# SCH_Ortho90_2023-07-25.net
KiCad netlist of a schematic drawn in EasyEDA
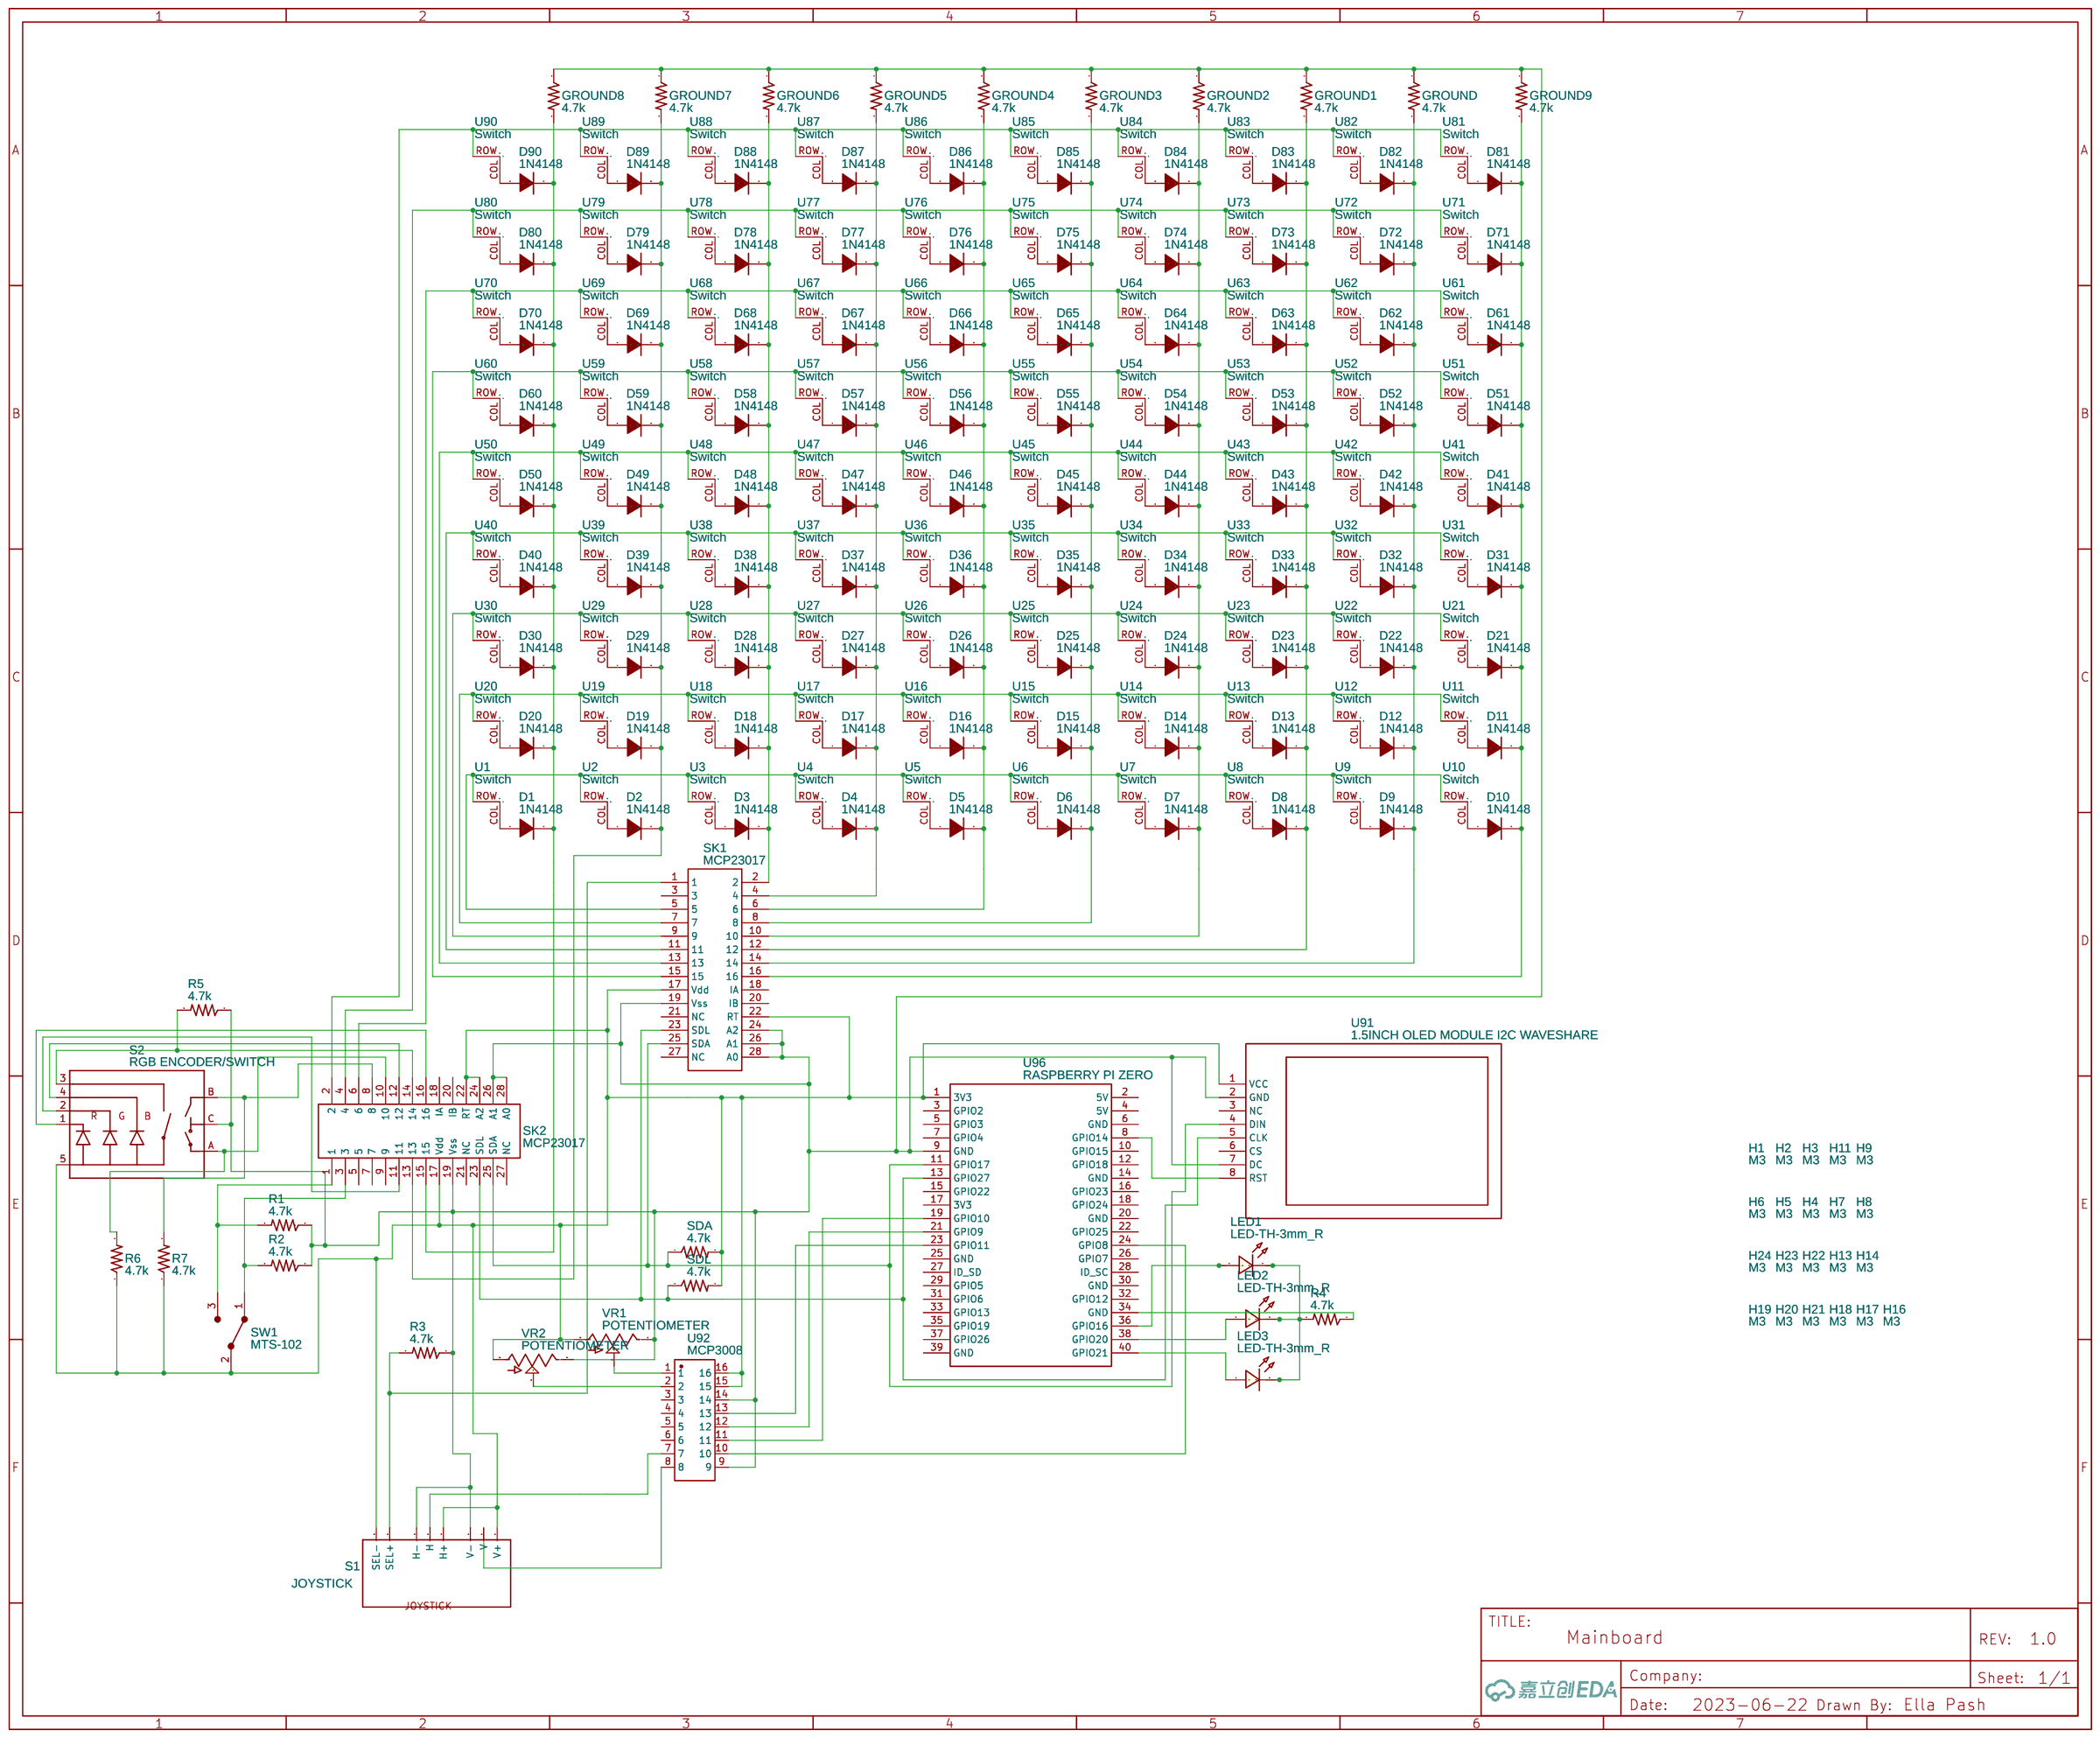
[diagram p0: schematic sheet]

(export (version "E")
  (design (tool "Eeschema 10.0.6"))
  (components
    (comp (ref "D1")
      (value "1N4148")
      (fields (field (name "BOM_Supplier Part") "C14516"))
      (libsource (lib "") (part "1N4148"))
    )
    (comp (ref "D2")
      (value "1N4148")
      (fields (field (name "BOM_Supplier Part") "C14516"))
      (libsource (lib "") (part "1N4148"))
    )
    (comp (ref "D3")
      (value "1N4148")
      (fields (field (name "BOM_Supplier Part") "C14516"))
      (libsource (lib "") (part "1N4148"))
    )
    (comp (ref "D4")
      (value "1N4148")
      (fields (field (name "BOM_Supplier Part") "C14516"))
      (libsource (lib "") (part "1N4148"))
    )
    (comp (ref "D5")
      (value "1N4148")
      (fields (field (name "BOM_Supplier Part") "C14516"))
      (libsource (lib "") (part "1N4148"))
    )
    (comp (ref "D6")
      (value "1N4148")
      (fields (field (name "BOM_Supplier Part") "C14516"))
      (libsource (lib "") (part "1N4148"))
    )
    (comp (ref "D7")
      (value "1N4148")
      (fields (field (name "BOM_Supplier Part") "C14516"))
      (libsource (lib "") (part "1N4148"))
    )
    (comp (ref "D8")
      (value "1N4148")
      (fields (field (name "BOM_Supplier Part") "C14516"))
      (libsource (lib "") (part "1N4148"))
    )
    (comp (ref "D9")
      (value "1N4148")
      (fields (field (name "BOM_Supplier Part") "C14516"))
      (libsource (lib "") (part "1N4148"))
    )
    (comp (ref "D10")
      (value "1N4148")
      (fields (field (name "BOM_Supplier Part") "C14516"))
      (libsource (lib "") (part "1N4148"))
    )
    (comp (ref "D11")
      (value "1N4148")
      (fields (field (name "BOM_Supplier Part") "C14516"))
      (libsource (lib "") (part "1N4148"))
    )
    (comp (ref "D12")
      (value "1N4148")
      (fields (field (name "BOM_Supplier Part") "C14516"))
      (libsource (lib "") (part "1N4148"))
    )
    (comp (ref "D13")
      (value "1N4148")
      (fields (field (name "BOM_Supplier Part") "C14516"))
      (libsource (lib "") (part "1N4148"))
    )
    (comp (ref "D14")
      (value "1N4148")
      (fields (field (name "BOM_Supplier Part") "C14516"))
      (libsource (lib "") (part "1N4148"))
    )
    (comp (ref "D15")
      (value "1N4148")
      (fields (field (name "BOM_Supplier Part") "C14516"))
      (libsource (lib "") (part "1N4148"))
    )
    (comp (ref "D16")
      (value "1N4148")
      (fields (field (name "BOM_Supplier Part") "C14516"))
      (libsource (lib "") (part "1N4148"))
    )
    (comp (ref "D17")
      (value "1N4148")
      (fields (field (name "BOM_Supplier Part") "C14516"))
      (libsource (lib "") (part "1N4148"))
    )
    (comp (ref "D18")
      (value "1N4148")
      (fields (field (name "BOM_Supplier Part") "C14516"))
      (libsource (lib "") (part "1N4148"))
    )
    (comp (ref "D19")
      (value "1N4148")
      (fields (field (name "BOM_Supplier Part") "C14516"))
      (libsource (lib "") (part "1N4148"))
    )
    (comp (ref "D20")
      (value "1N4148")
      (fields (field (name "BOM_Supplier Part") "C14516"))
      (libsource (lib "") (part "1N4148"))
    )
    (comp (ref "D21")
      (value "1N4148")
      (fields (field (name "BOM_Supplier Part") "C14516"))
      (libsource (lib "") (part "1N4148"))
    )
    (comp (ref "D22")
      (value "1N4148")
      (fields (field (name "BOM_Supplier Part") "C14516"))
      (libsource (lib "") (part "1N4148"))
    )
    (comp (ref "D23")
      (value "1N4148")
      (fields (field (name "BOM_Supplier Part") "C14516"))
      (libsource (lib "") (part "1N4148"))
    )
    (comp (ref "D24")
      (value "1N4148")
      (fields (field (name "BOM_Supplier Part") "C14516"))
      (libsource (lib "") (part "1N4148"))
    )
    (comp (ref "D25")
      (value "1N4148")
      (fields (field (name "BOM_Supplier Part") "C14516"))
      (libsource (lib "") (part "1N4148"))
    )
    (comp (ref "D26")
      (value "1N4148")
      (fields (field (name "BOM_Supplier Part") "C14516"))
      (libsource (lib "") (part "1N4148"))
    )
    (comp (ref "D27")
      (value "1N4148")
      (fields (field (name "BOM_Supplier Part") "C14516"))
      (libsource (lib "") (part "1N4148"))
    )
    (comp (ref "D28")
      (value "1N4148")
      (fields (field (name "BOM_Supplier Part") "C14516"))
      (libsource (lib "") (part "1N4148"))
    )
    (comp (ref "D29")
      (value "1N4148")
      (fields (field (name "BOM_Supplier Part") "C14516"))
      (libsource (lib "") (part "1N4148"))
    )
    (comp (ref "D30")
      (value "1N4148")
      (fields (field (name "BOM_Supplier Part") "C14516"))
      (libsource (lib "") (part "1N4148"))
    )
    (comp (ref "D31")
      (value "1N4148")
      (fields (field (name "BOM_Supplier Part") "C14516"))
      (libsource (lib "") (part "1N4148"))
    )
    (comp (ref "D32")
      (value "1N4148")
      (fields (field (name "BOM_Supplier Part") "C14516"))
      (libsource (lib "") (part "1N4148"))
    )
    (comp (ref "D33")
      (value "1N4148")
      (fields (field (name "BOM_Supplier Part") "C14516"))
      (libsource (lib "") (part "1N4148"))
    )
    (comp (ref "D34")
      (value "1N4148")
      (fields (field (name "BOM_Supplier Part") "C14516"))
      (libsource (lib "") (part "1N4148"))
    )
    (comp (ref "D35")
      (value "1N4148")
      (fields (field (name "BOM_Supplier Part") "C14516"))
      (libsource (lib "") (part "1N4148"))
    )
    (comp (ref "D36")
      (value "1N4148")
      (fields (field (name "BOM_Supplier Part") "C14516"))
      (libsource (lib "") (part "1N4148"))
    )
    (comp (ref "D37")
      (value "1N4148")
      (fields (field (name "BOM_Supplier Part") "C14516"))
      (libsource (lib "") (part "1N4148"))
    )
    (comp (ref "D38")
      (value "1N4148")
      (fields (field (name "BOM_Supplier Part") "C14516"))
      (libsource (lib "") (part "1N4148"))
    )
    (comp (ref "D39")
      (value "1N4148")
      (fields (field (name "BOM_Supplier Part") "C14516"))
      (libsource (lib "") (part "1N4148"))
    )
    (comp (ref "D40")
      (value "1N4148")
      (fields (field (name "BOM_Supplier Part") "C14516"))
      (libsource (lib "") (part "1N4148"))
    )
    (comp (ref "D41")
      (value "1N4148")
      (fields (field (name "BOM_Supplier Part") "C14516"))
      (libsource (lib "") (part "1N4148"))
    )
    (comp (ref "D42")
      (value "1N4148")
      (fields (field (name "BOM_Supplier Part") "C14516"))
      (libsource (lib "") (part "1N4148"))
    )
    (comp (ref "D43")
      (value "1N4148")
      (fields (field (name "BOM_Supplier Part") "C14516"))
      (libsource (lib "") (part "1N4148"))
    )
    (comp (ref "D44")
      (value "1N4148")
      (fields (field (name "BOM_Supplier Part") "C14516"))
      (libsource (lib "") (part "1N4148"))
    )
    (comp (ref "D45")
      (value "1N4148")
      (fields (field (name "BOM_Supplier Part") "C14516"))
      (libsource (lib "") (part "1N4148"))
    )
    (comp (ref "D46")
      (value "1N4148")
      (fields (field (name "BOM_Supplier Part") "C14516"))
      (libsource (lib "") (part "1N4148"))
    )
    (comp (ref "D47")
      (value "1N4148")
      (fields (field (name "BOM_Supplier Part") "C14516"))
      (libsource (lib "") (part "1N4148"))
    )
    (comp (ref "D48")
      (value "1N4148")
      (fields (field (name "BOM_Supplier Part") "C14516"))
      (libsource (lib "") (part "1N4148"))
    )
    (comp (ref "D49")
      (value "1N4148")
      (fields (field (name "BOM_Supplier Part") "C14516"))
      (libsource (lib "") (part "1N4148"))
    )
    (comp (ref "D50")
      (value "1N4148")
      (fields (field (name "BOM_Supplier Part") "C14516"))
      (libsource (lib "") (part "1N4148"))
    )
    (comp (ref "D51")
      (value "1N4148")
      (fields (field (name "BOM_Supplier Part") "C14516"))
      (libsource (lib "") (part "1N4148"))
    )
    (comp (ref "D52")
      (value "1N4148")
      (fields (field (name "BOM_Supplier Part") "C14516"))
      (libsource (lib "") (part "1N4148"))
    )
    (comp (ref "D53")
      (value "1N4148")
      (fields (field (name "BOM_Supplier Part") "C14516"))
      (libsource (lib "") (part "1N4148"))
    )
    (comp (ref "D54")
      (value "1N4148")
      (fields (field (name "BOM_Supplier Part") "C14516"))
      (libsource (lib "") (part "1N4148"))
    )
    (comp (ref "D55")
      (value "1N4148")
      (fields (field (name "BOM_Supplier Part") "C14516"))
      (libsource (lib "") (part "1N4148"))
    )
    (comp (ref "D56")
      (value "1N4148")
      (fields (field (name "BOM_Supplier Part") "C14516"))
      (libsource (lib "") (part "1N4148"))
    )
    (comp (ref "D57")
      (value "1N4148")
      (fields (field (name "BOM_Supplier Part") "C14516"))
      (libsource (lib "") (part "1N4148"))
    )
    (comp (ref "D58")
      (value "1N4148")
      (fields (field (name "BOM_Supplier Part") "C14516"))
      (libsource (lib "") (part "1N4148"))
    )
    (comp (ref "D59")
      (value "1N4148")
      (fields (field (name "BOM_Supplier Part") "C14516"))
      (libsource (lib "") (part "1N4148"))
    )
    (comp (ref "D60")
      (value "1N4148")
      (fields (field (name "BOM_Supplier Part") "C14516"))
      (libsource (lib "") (part "1N4148"))
    )
    (comp (ref "D61")
      (value "1N4148")
      (fields (field (name "BOM_Supplier Part") "C14516"))
      (libsource (lib "") (part "1N4148"))
    )
    (comp (ref "D62")
      (value "1N4148")
      (fields (field (name "BOM_Supplier Part") "C14516"))
      (libsource (lib "") (part "1N4148"))
    )
    (comp (ref "D63")
      (value "1N4148")
      (fields (field (name "BOM_Supplier Part") "C14516"))
      (libsource (lib "") (part "1N4148"))
    )
    (comp (ref "D64")
      (value "1N4148")
      (fields (field (name "BOM_Supplier Part") "C14516"))
      (libsource (lib "") (part "1N4148"))
    )
    (comp (ref "D65")
      (value "1N4148")
      (fields (field (name "BOM_Supplier Part") "C14516"))
      (libsource (lib "") (part "1N4148"))
    )
    (comp (ref "D66")
      (value "1N4148")
      (fields (field (name "BOM_Supplier Part") "C14516"))
      (libsource (lib "") (part "1N4148"))
    )
    (comp (ref "D67")
      (value "1N4148")
      (fields (field (name "BOM_Supplier Part") "C14516"))
      (libsource (lib "") (part "1N4148"))
    )
    (comp (ref "D68")
      (value "1N4148")
      (fields (field (name "BOM_Supplier Part") "C14516"))
      (libsource (lib "") (part "1N4148"))
    )
    (comp (ref "D69")
      (value "1N4148")
      (fields (field (name "BOM_Supplier Part") "C14516"))
      (libsource (lib "") (part "1N4148"))
    )
    (comp (ref "D70")
      (value "1N4148")
      (fields (field (name "BOM_Supplier Part") "C14516"))
      (libsource (lib "") (part "1N4148"))
    )
    (comp (ref "D71")
      (value "1N4148")
      (fields (field (name "BOM_Supplier Part") "C14516"))
      (libsource (lib "") (part "1N4148"))
    )
    (comp (ref "D72")
      (value "1N4148")
      (fields (field (name "BOM_Supplier Part") "C14516"))
      (libsource (lib "") (part "1N4148"))
    )
    (comp (ref "D73")
      (value "1N4148")
      (fields (field (name "BOM_Supplier Part") "C14516"))
      (libsource (lib "") (part "1N4148"))
    )
    (comp (ref "D74")
      (value "1N4148")
      (fields (field (name "BOM_Supplier Part") "C14516"))
      (libsource (lib "") (part "1N4148"))
    )
    (comp (ref "D75")
      (value "1N4148")
      (fields (field (name "BOM_Supplier Part") "C14516"))
      (libsource (lib "") (part "1N4148"))
    )
    (comp (ref "D76")
      (value "1N4148")
      (fields (field (name "BOM_Supplier Part") "C14516"))
      (libsource (lib "") (part "1N4148"))
    )
    (comp (ref "D77")
      (value "1N4148")
      (fields (field (name "BOM_Supplier Part") "C14516"))
      (libsource (lib "") (part "1N4148"))
    )
    (comp (ref "D78")
      (value "1N4148")
      (fields (field (name "BOM_Supplier Part") "C14516"))
      (libsource (lib "") (part "1N4148"))
    )
    (comp (ref "D79")
      (value "1N4148")
      (fields (field (name "BOM_Supplier Part") "C14516"))
      (libsource (lib "") (part "1N4148"))
    )
    (comp (ref "D80")
      (value "1N4148")
      (fields (field (name "BOM_Supplier Part") "C14516"))
      (libsource (lib "") (part "1N4148"))
    )
    (comp (ref "D81")
      (value "1N4148")
      (fields (field (name "BOM_Supplier Part") "C14516"))
      (libsource (lib "") (part "1N4148"))
    )
    (comp (ref "D82")
      (value "1N4148")
      (fields (field (name "BOM_Supplier Part") "C14516"))
      (libsource (lib "") (part "1N4148"))
    )
    (comp (ref "D83")
      (value "1N4148")
      (fields (field (name "BOM_Supplier Part") "C14516"))
      (libsource (lib "") (part "1N4148"))
    )
    (comp (ref "D84")
      (value "1N4148")
      (fields (field (name "BOM_Supplier Part") "C14516"))
      (libsource (lib "") (part "1N4148"))
    )
    (comp (ref "D85")
      (value "1N4148")
      (fields (field (name "BOM_Supplier Part") "C14516"))
      (libsource (lib "") (part "1N4148"))
    )
    (comp (ref "D86")
      (value "1N4148")
      (fields (field (name "BOM_Supplier Part") "C14516"))
      (libsource (lib "") (part "1N4148"))
    )
    (comp (ref "D87")
      (value "1N4148")
      (fields (field (name "BOM_Supplier Part") "C14516"))
      (libsource (lib "") (part "1N4148"))
    )
    (comp (ref "D88")
      (value "1N4148")
      (fields (field (name "BOM_Supplier Part") "C14516"))
      (libsource (lib "") (part "1N4148"))
    )
    (comp (ref "D89")
      (value "1N4148")
      (fields (field (name "BOM_Supplier Part") "C14516"))
      (libsource (lib "") (part "1N4148"))
    )
    (comp (ref "D90")
      (value "1N4148")
      (fields (field (name "BOM_Supplier Part") "C14516"))
      (libsource (lib "") (part "1N4148"))
    )
    (comp (ref "GROUND") (value "4.7k") (libsource (lib "") (part "RESISTORKIT_1")))
    (comp (ref "GROUND1") (value "4.7k") (libsource (lib "") (part "RESISTORKIT_1")))
    (comp (ref "GROUND2") (value "4.7k") (libsource (lib "") (part "RESISTORKIT_1")))
    (comp (ref "GROUND3") (value "4.7k") (libsource (lib "") (part "RESISTORKIT_1")))
    (comp (ref "GROUND4") (value "4.7k") (libsource (lib "") (part "RESISTORKIT_1")))
    (comp (ref "GROUND5") (value "4.7k") (libsource (lib "") (part "RESISTORKIT_1")))
    (comp (ref "GROUND6") (value "4.7k") (libsource (lib "") (part "RESISTORKIT_1")))
    (comp (ref "GROUND7") (value "4.7k") (libsource (lib "") (part "RESISTORKIT_1")))
    (comp (ref "GROUND8") (value "4.7k") (libsource (lib "") (part "RESISTORKIT_1")))
    (comp (ref "GROUND9") (value "4.7k") (libsource (lib "") (part "RESISTORKIT_1")))
    (comp (ref "H1") (value "M3") (libsource (lib "") (part "MountingHole_3.2mm_M3")))
    (comp (ref "H2") (value "M3") (libsource (lib "") (part "MountingHole_3.2mm_M3")))
    (comp (ref "H3") (value "M3") (libsource (lib "") (part "MountingHole_3.2mm_M3")))
    (comp (ref "H4") (value "M3") (libsource (lib "") (part "MountingHole_3.2mm_M3")))
    (comp (ref "H5") (value "M3") (libsource (lib "") (part "MountingHole_3.2mm_M3")))
    (comp (ref "H6") (value "M3") (libsource (lib "") (part "MountingHole_3.2mm_M3")))
    (comp (ref "H7") (value "M3") (libsource (lib "") (part "MountingHole_3.2mm_M3")))
    (comp (ref "H8") (value "M3") (libsource (lib "") (part "MountingHole_3.2mm_M3")))
    (comp (ref "H9") (value "M3") (libsource (lib "") (part "MountingHole_3.2mm_M3")))
    (comp (ref "H11") (value "M3") (libsource (lib "") (part "MountingHole_3.2mm_M3")))
    (comp (ref "H13") (value "M3") (libsource (lib "") (part "MountingHole_3.2mm_M3")))
    (comp (ref "H14") (value "M3") (libsource (lib "") (part "MountingHole_3.2mm_M3")))
    (comp (ref "H16") (value "M3") (libsource (lib "") (part "MountingHole_3.2mm_M3")))
    (comp (ref "H17") (value "M3") (libsource (lib "") (part "MountingHole_3.2mm_M3")))
    (comp (ref "H18") (value "M3") (libsource (lib "") (part "MountingHole_3.2mm_M3")))
    (comp (ref "H19") (value "M3") (libsource (lib "") (part "MountingHole_3.2mm_M3")))
    (comp (ref "H20") (value "M3") (libsource (lib "") (part "MountingHole_3.2mm_M3")))
    (comp (ref "H21") (value "M3") (libsource (lib "") (part "MountingHole_3.2mm_M3")))
    (comp (ref "H22") (value "M3") (libsource (lib "") (part "MountingHole_3.2mm_M3")))
    (comp (ref "H23") (value "M3") (libsource (lib "") (part "MountingHole_3.2mm_M3")))
    (comp (ref "H24") (value "M3") (libsource (lib "") (part "MountingHole_3.2mm_M3")))
    (comp (ref "LED1")
      (value "LED-TH-3mm_R")
      (fields
        (field (name "BOM_Manufacturer Part") "204-10SDRD/S530-A3-L")
        (field (name "BOM_Supplier Part") "C84774")
      )
      (libsource (lib "") (part "LED-TH-3mm_R"))
    )
    (comp (ref "LED2")
      (value "LED-TH-3mm_R")
      (fields
        (field (name "BOM_Manufacturer Part") "204-10SDRD/S530-A3-L")
        (field (name "BOM_Supplier Part") "C84774")
      )
      (libsource (lib "") (part "LED-TH-3mm_R"))
    )
    (comp (ref "LED3")
      (value "LED-TH-3mm_R")
      (fields
        (field (name "BOM_Manufacturer Part") "204-10SDRD/S530-A3-L")
        (field (name "BOM_Supplier Part") "C84774")
      )
      (libsource (lib "") (part "LED-TH-3mm_R"))
    )
    (comp (ref "R1") (value "4.7k") (libsource (lib "") (part "RESISTORKIT")))
    (comp (ref "R2") (value "4.7k") (libsource (lib "") (part "RESISTORKIT")))
    (comp (ref "R3") (value "4.7k") (libsource (lib "") (part "RESISTORKIT")))
    (comp (ref "R4") (value "4.7k") (libsource (lib "") (part "RESISTORKIT")))
    (comp (ref "R5") (value "4.7k") (libsource (lib "") (part "RESISTORKIT")))
    (comp (ref "R6") (value "4.7k") (libsource (lib "") (part "RESISTORKIT_2")))
    (comp (ref "R7") (value "4.7k") (libsource (lib "") (part "RESISTORKIT_2")))
    (comp (ref "S1") (value "JOYSTICK") (libsource (lib "") (part "JOYSTICK_THUMB")))
    (comp (ref "S2") (value "RGB ENCODER/SWITCH") (libsource (lib "") (part "ENCODER-RGB-SWITCH-NO_NUT")))
    (comp (ref "SDA") (value "4.7k") (libsource (lib "") (part "RESISTORKIT_3")))
    (comp (ref "SDL") (value "4.7k") (libsource (lib "") (part "RESISTORKIT_4")))
    (comp (ref "SK1")
      (value "MCP23017")
      (fields (field (name "BOM_Manufacturer Part") "IC-28P窄") (field (name "BOM_Supplier Part") "C16653"))
      (libsource (lib "") (part "IC seat_1"))
    )
    (comp (ref "SK2")
      (value "MCP23017")
      (fields (field (name "BOM_Manufacturer Part") "IC-28P窄") (field (name "BOM_Supplier Part") "C16653"))
      (libsource (lib "") (part "IC seat"))
    )
    (comp (ref "SW1")
      (value "MTS-102")
      (fields
        (field (name "BOM_Manufacturer Part") "New SchematicLib")
        (field (name "BOM_Supplier Part") "SMTS-202-A2")
      )
      (libsource (lib "") (part "MTS-102"))
    )
    (comp (ref "U1") (value "Switch") (libsource (lib "") (part "Switch")))
    (comp (ref "U2") (value "Switch") (libsource (lib "") (part "Switch")))
    (comp (ref "U3") (value "Switch") (libsource (lib "") (part "Switch")))
    (comp (ref "U4") (value "Switch") (libsource (lib "") (part "Switch")))
    (comp (ref "U5") (value "Switch") (libsource (lib "") (part "Switch")))
    (comp (ref "U6") (value "Switch") (libsource (lib "") (part "Switch")))
    (comp (ref "U7") (value "Switch") (libsource (lib "") (part "Switch")))
    (comp (ref "U8") (value "Switch") (libsource (lib "") (part "Switch")))
    (comp (ref "U9") (value "Switch") (libsource (lib "") (part "Switch")))
    (comp (ref "U10") (value "Switch") (libsource (lib "") (part "Switch")))
    (comp (ref "U11") (value "Switch") (libsource (lib "") (part "Switch")))
    (comp (ref "U12") (value "Switch") (libsource (lib "") (part "Switch")))
    (comp (ref "U13") (value "Switch") (libsource (lib "") (part "Switch")))
    (comp (ref "U14") (value "Switch") (libsource (lib "") (part "Switch")))
    (comp (ref "U15") (value "Switch") (libsource (lib "") (part "Switch")))
    (comp (ref "U16") (value "Switch") (libsource (lib "") (part "Switch")))
    (comp (ref "U17") (value "Switch") (libsource (lib "") (part "Switch")))
    (comp (ref "U18") (value "Switch") (libsource (lib "") (part "Switch")))
    (comp (ref "U19") (value "Switch") (libsource (lib "") (part "Switch")))
    (comp (ref "U20") (value "Switch") (libsource (lib "") (part "Switch")))
    (comp (ref "U21") (value "Switch") (libsource (lib "") (part "Switch")))
    (comp (ref "U22") (value "Switch") (libsource (lib "") (part "Switch")))
    (comp (ref "U23") (value "Switch") (libsource (lib "") (part "Switch")))
    (comp (ref "U24") (value "Switch") (libsource (lib "") (part "Switch")))
    (comp (ref "U25") (value "Switch") (libsource (lib "") (part "Switch")))
    (comp (ref "U26") (value "Switch") (libsource (lib "") (part "Switch")))
    (comp (ref "U27") (value "Switch") (libsource (lib "") (part "Switch")))
    (comp (ref "U28") (value "Switch") (libsource (lib "") (part "Switch")))
    (comp (ref "U29") (value "Switch") (libsource (lib "") (part "Switch")))
    (comp (ref "U30") (value "Switch") (libsource (lib "") (part "Switch")))
    (comp (ref "U31") (value "Switch") (libsource (lib "") (part "Switch")))
    (comp (ref "U32") (value "Switch") (libsource (lib "") (part "Switch")))
    (comp (ref "U33") (value "Switch") (libsource (lib "") (part "Switch")))
    (comp (ref "U34") (value "Switch") (libsource (lib "") (part "Switch")))
    (comp (ref "U35") (value "Switch") (libsource (lib "") (part "Switch")))
    (comp (ref "U36") (value "Switch") (libsource (lib "") (part "Switch")))
    (comp (ref "U37") (value "Switch") (libsource (lib "") (part "Switch")))
    (comp (ref "U38") (value "Switch") (libsource (lib "") (part "Switch")))
    (comp (ref "U39") (value "Switch") (libsource (lib "") (part "Switch")))
    (comp (ref "U40") (value "Switch") (libsource (lib "") (part "Switch")))
    (comp (ref "U41") (value "Switch") (libsource (lib "") (part "Switch")))
    (comp (ref "U42") (value "Switch") (libsource (lib "") (part "Switch")))
    (comp (ref "U43") (value "Switch") (libsource (lib "") (part "Switch")))
    (comp (ref "U44") (value "Switch") (libsource (lib "") (part "Switch")))
    (comp (ref "U45") (value "Switch") (libsource (lib "") (part "Switch")))
    (comp (ref "U46") (value "Switch") (libsource (lib "") (part "Switch")))
    (comp (ref "U47") (value "Switch") (libsource (lib "") (part "Switch")))
    (comp (ref "U48") (value "Switch") (libsource (lib "") (part "Switch")))
    (comp (ref "U49") (value "Switch") (libsource (lib "") (part "Switch")))
    (comp (ref "U50") (value "Switch") (libsource (lib "") (part "Switch")))
    (comp (ref "U51") (value "Switch") (libsource (lib "") (part "Switch")))
    (comp (ref "U52") (value "Switch") (libsource (lib "") (part "Switch")))
    (comp (ref "U53") (value "Switch") (libsource (lib "") (part "Switch")))
    (comp (ref "U54") (value "Switch") (libsource (lib "") (part "Switch")))
    (comp (ref "U55") (value "Switch") (libsource (lib "") (part "Switch")))
    (comp (ref "U56") (value "Switch") (libsource (lib "") (part "Switch")))
    (comp (ref "U57") (value "Switch") (libsource (lib "") (part "Switch")))
    (comp (ref "U58") (value "Switch") (libsource (lib "") (part "Switch")))
    (comp (ref "U59") (value "Switch") (libsource (lib "") (part "Switch")))
    (comp (ref "U60") (value "Switch") (libsource (lib "") (part "Switch")))
    (comp (ref "U61") (value "Switch") (libsource (lib "") (part "Switch")))
    (comp (ref "U62") (value "Switch") (libsource (lib "") (part "Switch")))
    (comp (ref "U63") (value "Switch") (libsource (lib "") (part "Switch")))
    (comp (ref "U64") (value "Switch") (libsource (lib "") (part "Switch")))
    (comp (ref "U65") (value "Switch") (libsource (lib "") (part "Switch")))
    (comp (ref "U66") (value "Switch") (libsource (lib "") (part "Switch")))
    (comp (ref "U67") (value "Switch") (libsource (lib "") (part "Switch")))
    (comp (ref "U68") (value "Switch") (libsource (lib "") (part "Switch")))
    (comp (ref "U69") (value "Switch") (libsource (lib "") (part "Switch")))
    (comp (ref "U70") (value "Switch") (libsource (lib "") (part "Switch")))
    (comp (ref "U71") (value "Switch") (libsource (lib "") (part "Switch")))
    (comp (ref "U72") (value "Switch") (libsource (lib "") (part "Switch")))
    (comp (ref "U73") (value "Switch") (libsource (lib "") (part "Switch")))
    (comp (ref "U74") (value "Switch") (libsource (lib "") (part "Switch")))
    (comp (ref "U75") (value "Switch") (libsource (lib "") (part "Switch")))
    (comp (ref "U76") (value "Switch") (libsource (lib "") (part "Switch")))
    (comp (ref "U77") (value "Switch") (libsource (lib "") (part "Switch")))
    (comp (ref "U78") (value "Switch") (libsource (lib "") (part "Switch")))
    (comp (ref "U79") (value "Switch") (libsource (lib "") (part "Switch")))
    (comp (ref "U80") (value "Switch") (libsource (lib "") (part "Switch")))
    (comp (ref "U81") (value "Switch") (libsource (lib "") (part "Switch")))
    (comp (ref "U82") (value "Switch") (libsource (lib "") (part "Switch")))
    (comp (ref "U83") (value "Switch") (libsource (lib "") (part "Switch")))
    (comp (ref "U84") (value "Switch") (libsource (lib "") (part "Switch")))
    (comp (ref "U85") (value "Switch") (libsource (lib "") (part "Switch")))
    (comp (ref "U86") (value "Switch") (libsource (lib "") (part "Switch")))
    (comp (ref "U87") (value "Switch") (libsource (lib "") (part "Switch")))
    (comp (ref "U88") (value "Switch") (libsource (lib "") (part "Switch")))
    (comp (ref "U89") (value "Switch") (libsource (lib "") (part "Switch")))
    (comp (ref "U90") (value "Switch") (libsource (lib "") (part "Switch")))
    (comp (ref "U91")
      (value "1.5INCH OLED MODULE I2C WAVESHARE")
      (fields (field (name "BOM_Manufacturer Part") "Waveshare"))
      (libsource (lib "") (part "1.5INCH OLED MODULE SPI-I2C WAVESHARE (HOLE D3.2MM)"))
    )
    (comp (ref "U92")
      (value "MCP3008")
      (fields (field (name "BOM_Manufacturer Part") "IC-16P") (field (name "BOM_Supplier Part") "C5289487"))
      (libsource (lib "") (part "IC-16P"))
    )
    (comp (ref "U96") (value "RASPBERRY PI ZERO") (libsource (lib "") (part "Raspberry-PiZero-W")))
    (comp (ref "VR1") (value "POTENTIOMETER") (libsource (lib "") (part "POTENTIOMETER-PTH-9MM-1/20W-20%")))
    (comp (ref "VR2") (value "POTENTIOMETER") (libsource (lib "") (part "POTENTIOMETER-PTH-9MM-1/20W-20%")))
  )
  (nets
    (net (code "1") (name "Net-(D1-A)") (class "Default")
      (node (ref "D1") (pin "1") (pinfunction "A_1") (pintype "unspecified"))
      (node (ref "U1") (pin "COL") (pinfunction "2_COL") (pintype "unspecified"))
    )
    (net (code "2") (name "Net-(D1-C)") (class "Default")
      (node (ref "D1") (pin "2") (pinfunction "C_2") (pintype "unspecified"))
      (node (ref "D20") (pin "2") (pinfunction "C_2") (pintype "unspecified"))
      (node (ref "D30") (pin "2") (pinfunction "C_2") (pintype "unspecified"))
      (node (ref "D40") (pin "2") (pinfunction "C_2") (pintype "unspecified"))
      (node (ref "D50") (pin "2") (pinfunction "C_2") (pintype "unspecified"))
      (node (ref "D60") (pin "2") (pinfunction "C_2") (pintype "unspecified"))
      (node (ref "D70") (pin "2") (pinfunction "C_2") (pintype "unspecified"))
      (node (ref "D80") (pin "2") (pinfunction "C_2") (pintype "unspecified"))
      (node (ref "D90") (pin "2") (pinfunction "C_2") (pintype "unspecified"))
      (node (ref "GROUND8") (pin "2") (pinfunction "2_2") (pintype "unspecified"))
      (node (ref "SK2") (pin "15") (pinfunction "15_15") (pintype "unspecified"))
    )
    (net (code "3") (name "Net-(D2-A)") (class "Default")
      (node (ref "D2") (pin "1") (pinfunction "A_1") (pintype "unspecified"))
      (node (ref "U2") (pin "COL") (pinfunction "2_COL") (pintype "unspecified"))
    )
    (net (code "4") (name "Net-(D3-A)") (class "Default")
      (node (ref "D3") (pin "1") (pinfunction "A_1") (pintype "unspecified"))
      (node (ref "U3") (pin "COL") (pinfunction "2_COL") (pintype "unspecified"))
    )
    (net (code "5") (name "Net-(D4-A)") (class "Default")
      (node (ref "D4") (pin "1") (pinfunction "A_1") (pintype "unspecified"))
      (node (ref "U4") (pin "COL") (pinfunction "2_COL") (pintype "unspecified"))
    )
    (net (code "6") (name "Net-(D5-A)") (class "Default")
      (node (ref "D5") (pin "1") (pinfunction "A_1") (pintype "unspecified"))
      (node (ref "U5") (pin "COL") (pinfunction "2_COL") (pintype "unspecified"))
    )
    (net (code "7") (name "Net-(D6-A)") (class "Default")
      (node (ref "D6") (pin "1") (pinfunction "A_1") (pintype "unspecified"))
      (node (ref "U6") (pin "COL") (pinfunction "2_COL") (pintype "unspecified"))
    )
    (net (code "8") (name "Net-(D7-A)") (class "Default")
      (node (ref "D7") (pin "1") (pinfunction "A_1") (pintype "unspecified"))
      (node (ref "U7") (pin "COL") (pinfunction "2_COL") (pintype "unspecified"))
    )
    (net (code "9") (name "Net-(D8-A)") (class "Default")
      (node (ref "D8") (pin "1") (pinfunction "A_1") (pintype "unspecified"))
      (node (ref "U8") (pin "COL") (pinfunction "2_COL") (pintype "unspecified"))
    )
    (net (code "10") (name "Net-(D9-A)") (class "Default")
      (node (ref "D9") (pin "1") (pinfunction "A_1") (pintype "unspecified"))
      (node (ref "U9") (pin "COL") (pinfunction "2_COL") (pintype "unspecified"))
    )
    (net (code "11") (name "Net-(D10-A)") (class "Default")
      (node (ref "D10") (pin "1") (pinfunction "A_1") (pintype "unspecified"))
      (node (ref "U10") (pin "COL") (pinfunction "2_COL") (pintype "unspecified"))
    )
    (net (code "12") (name "Net-(D10-C)") (class "Default")
      (node (ref "D10") (pin "2") (pinfunction "C_2") (pintype "unspecified"))
      (node (ref "D11") (pin "2") (pinfunction "C_2") (pintype "unspecified"))
      (node (ref "D21") (pin "2") (pinfunction "C_2") (pintype "unspecified"))
      (node (ref "D31") (pin "2") (pinfunction "C_2") (pintype "unspecified"))
      (node (ref "D41") (pin "2") (pinfunction "C_2") (pintype "unspecified"))
      (node (ref "D51") (pin "2") (pinfunction "C_2") (pintype "unspecified"))
      (node (ref "D61") (pin "2") (pinfunction "C_2") (pintype "unspecified"))
      (node (ref "D71") (pin "2") (pinfunction "C_2") (pintype "unspecified"))
      (node (ref "D81") (pin "2") (pinfunction "C_2") (pintype "unspecified"))
      (node (ref "GROUND9") (pin "2") (pinfunction "2_2") (pintype "unspecified"))
      (node (ref "SK1") (pin "16") (pinfunction "16_16") (pintype "unspecified"))
    )
    (net (code "13") (name "Net-(D11-A)") (class "Default")
      (node (ref "D11") (pin "1") (pinfunction "A_1") (pintype "unspecified"))
      (node (ref "U11") (pin "COL") (pinfunction "2_COL") (pintype "unspecified"))
    )
    (net (code "14") (name "Net-(D12-A)") (class "Default")
      (node (ref "D12") (pin "1") (pinfunction "A_1") (pintype "unspecified"))
      (node (ref "U12") (pin "COL") (pinfunction "2_COL") (pintype "unspecified"))
    )
    (net (code "15") (name "Net-(D12-C)") (class "Default")
      (node (ref "D12") (pin "2") (pinfunction "C_2") (pintype "unspecified"))
      (node (ref "D22") (pin "2") (pinfunction "C_2") (pintype "unspecified"))
      (node (ref "D32") (pin "2") (pinfunction "C_2") (pintype "unspecified"))
      (node (ref "D42") (pin "2") (pinfunction "C_2") (pintype "unspecified"))
      (node (ref "D52") (pin "2") (pinfunction "C_2") (pintype "unspecified"))
      (node (ref "D62") (pin "2") (pinfunction "C_2") (pintype "unspecified"))
      (node (ref "D72") (pin "2") (pinfunction "C_2") (pintype "unspecified"))
      (node (ref "D82") (pin "2") (pinfunction "C_2") (pintype "unspecified"))
      (node (ref "D9") (pin "2") (pinfunction "C_2") (pintype "unspecified"))
      (node (ref "GROUND") (pin "2") (pinfunction "2_2") (pintype "unspecified"))
      (node (ref "SK1") (pin "14") (pinfunction "14_14") (pintype "unspecified"))
    )
    (net (code "16") (name "Net-(D13-A)") (class "Default")
      (node (ref "D13") (pin "1") (pinfunction "A_1") (pintype "unspecified"))
      (node (ref "U13") (pin "COL") (pinfunction "2_COL") (pintype "unspecified"))
    )
    (net (code "17") (name "Net-(D13-C)") (class "Default")
      (node (ref "D13") (pin "2") (pinfunction "C_2") (pintype "unspecified"))
      (node (ref "D23") (pin "2") (pinfunction "C_2") (pintype "unspecified"))
      (node (ref "D33") (pin "2") (pinfunction "C_2") (pintype "unspecified"))
      (node (ref "D43") (pin "2") (pinfunction "C_2") (pintype "unspecified"))
      (node (ref "D53") (pin "2") (pinfunction "C_2") (pintype "unspecified"))
      (node (ref "D63") (pin "2") (pinfunction "C_2") (pintype "unspecified"))
      (node (ref "D73") (pin "2") (pinfunction "C_2") (pintype "unspecified"))
      (node (ref "D8") (pin "2") (pinfunction "C_2") (pintype "unspecified"))
      (node (ref "D83") (pin "2") (pinfunction "C_2") (pintype "unspecified"))
      (node (ref "GROUND1") (pin "2") (pinfunction "2_2") (pintype "unspecified"))
      (node (ref "SK1") (pin "12") (pinfunction "12_12") (pintype "unspecified"))
    )
    (net (code "18") (name "Net-(D14-A)") (class "Default")
      (node (ref "D14") (pin "1") (pinfunction "A_1") (pintype "unspecified"))
      (node (ref "U14") (pin "COL") (pinfunction "2_COL") (pintype "unspecified"))
    )
    (net (code "19") (name "Net-(D14-C)") (class "Default")
      (node (ref "D14") (pin "2") (pinfunction "C_2") (pintype "unspecified"))
      (node (ref "D24") (pin "2") (pinfunction "C_2") (pintype "unspecified"))
      (node (ref "D34") (pin "2") (pinfunction "C_2") (pintype "unspecified"))
      (node (ref "D44") (pin "2") (pinfunction "C_2") (pintype "unspecified"))
      (node (ref "D54") (pin "2") (pinfunction "C_2") (pintype "unspecified"))
      (node (ref "D64") (pin "2") (pinfunction "C_2") (pintype "unspecified"))
      (node (ref "D7") (pin "2") (pinfunction "C_2") (pintype "unspecified"))
      (node (ref "D74") (pin "2") (pinfunction "C_2") (pintype "unspecified"))
      (node (ref "D84") (pin "2") (pinfunction "C_2") (pintype "unspecified"))
      (node (ref "GROUND2") (pin "2") (pinfunction "2_2") (pintype "unspecified"))
      (node (ref "SK1") (pin "10") (pinfunction "10_10") (pintype "unspecified"))
    )
    (net (code "20") (name "Net-(D15-A)") (class "Default")
      (node (ref "D15") (pin "1") (pinfunction "A_1") (pintype "unspecified"))
      (node (ref "U15") (pin "COL") (pinfunction "2_COL") (pintype "unspecified"))
    )
    (net (code "21") (name "Net-(D15-C)") (class "Default")
      (node (ref "D15") (pin "2") (pinfunction "C_2") (pintype "unspecified"))
      (node (ref "D25") (pin "2") (pinfunction "C_2") (pintype "unspecified"))
      (node (ref "D35") (pin "2") (pinfunction "C_2") (pintype "unspecified"))
      (node (ref "D45") (pin "2") (pinfunction "C_2") (pintype "unspecified"))
      (node (ref "D55") (pin "2") (pinfunction "C_2") (pintype "unspecified"))
      (node (ref "D6") (pin "2") (pinfunction "C_2") (pintype "unspecified"))
      (node (ref "D65") (pin "2") (pinfunction "C_2") (pintype "unspecified"))
      (node (ref "D75") (pin "2") (pinfunction "C_2") (pintype "unspecified"))
      (node (ref "D85") (pin "2") (pinfunction "C_2") (pintype "unspecified"))
      (node (ref "GROUND3") (pin "2") (pinfunction "2_2") (pintype "unspecified"))
      (node (ref "SK1") (pin "8") (pinfunction "8_8") (pintype "unspecified"))
    )
    (net (code "22") (name "Net-(D16-A)") (class "Default")
      (node (ref "D16") (pin "1") (pinfunction "A_1") (pintype "unspecified"))
      (node (ref "U16") (pin "COL") (pinfunction "2_COL") (pintype "unspecified"))
    )
    (net (code "23") (name "Net-(D16-C)") (class "Default")
      (node (ref "D16") (pin "2") (pinfunction "C_2") (pintype "unspecified"))
      (node (ref "D26") (pin "2") (pinfunction "C_2") (pintype "unspecified"))
      (node (ref "D36") (pin "2") (pinfunction "C_2") (pintype "unspecified"))
      (node (ref "D46") (pin "2") (pinfunction "C_2") (pintype "unspecified"))
      (node (ref "D5") (pin "2") (pinfunction "C_2") (pintype "unspecified"))
      (node (ref "D56") (pin "2") (pinfunction "C_2") (pintype "unspecified"))
      (node (ref "D66") (pin "2") (pinfunction "C_2") (pintype "unspecified"))
      (node (ref "D76") (pin "2") (pinfunction "C_2") (pintype "unspecified"))
      (node (ref "D86") (pin "2") (pinfunction "C_2") (pintype "unspecified"))
      (node (ref "GROUND4") (pin "2") (pinfunction "2_2") (pintype "unspecified"))
      (node (ref "SK1") (pin "6") (pinfunction "6_6") (pintype "unspecified"))
    )
    (net (code "24") (name "Net-(D17-A)") (class "Default")
      (node (ref "D17") (pin "1") (pinfunction "A_1") (pintype "unspecified"))
      (node (ref "U17") (pin "COL") (pinfunction "2_COL") (pintype "unspecified"))
    )
    (net (code "25") (name "Net-(D17-C)") (class "Default")
      (node (ref "D17") (pin "2") (pinfunction "C_2") (pintype "unspecified"))
      (node (ref "D27") (pin "2") (pinfunction "C_2") (pintype "unspecified"))
      (node (ref "D37") (pin "2") (pinfunction "C_2") (pintype "unspecified"))
      (node (ref "D4") (pin "2") (pinfunction "C_2") (pintype "unspecified"))
      (node (ref "D47") (pin "2") (pinfunction "C_2") (pintype "unspecified"))
      (node (ref "D57") (pin "2") (pinfunction "C_2") (pintype "unspecified"))
      (node (ref "D67") (pin "2") (pinfunction "C_2") (pintype "unspecified"))
      (node (ref "D77") (pin "2") (pinfunction "C_2") (pintype "unspecified"))
      (node (ref "D87") (pin "2") (pinfunction "C_2") (pintype "unspecified"))
      (node (ref "GROUND5") (pin "2") (pinfunction "2_2") (pintype "unspecified"))
      (node (ref "SK1") (pin "4") (pinfunction "4_4") (pintype "unspecified"))
    )
    (net (code "26") (name "Net-(D18-A)") (class "Default")
      (node (ref "D18") (pin "1") (pinfunction "A_1") (pintype "unspecified"))
      (node (ref "U18") (pin "COL") (pinfunction "2_COL") (pintype "unspecified"))
    )
    (net (code "27") (name "Net-(D18-C)") (class "Default")
      (node (ref "D18") (pin "2") (pinfunction "C_2") (pintype "unspecified"))
      (node (ref "D28") (pin "2") (pinfunction "C_2") (pintype "unspecified"))
      (node (ref "D3") (pin "2") (pinfunction "C_2") (pintype "unspecified"))
      (node (ref "D38") (pin "2") (pinfunction "C_2") (pintype "unspecified"))
      (node (ref "D48") (pin "2") (pinfunction "C_2") (pintype "unspecified"))
      (node (ref "D58") (pin "2") (pinfunction "C_2") (pintype "unspecified"))
      (node (ref "D68") (pin "2") (pinfunction "C_2") (pintype "unspecified"))
      (node (ref "D78") (pin "2") (pinfunction "C_2") (pintype "unspecified"))
      (node (ref "D88") (pin "2") (pinfunction "C_2") (pintype "unspecified"))
      (node (ref "GROUND6") (pin "2") (pinfunction "2_2") (pintype "unspecified"))
      (node (ref "SK1") (pin "2") (pinfunction "2_2") (pintype "unspecified"))
    )
    (net (code "28") (name "Net-(D19-A)") (class "Default")
      (node (ref "D19") (pin "1") (pinfunction "A_1") (pintype "unspecified"))
      (node (ref "U19") (pin "COL") (pinfunction "2_COL") (pintype "unspecified"))
    )
    (net (code "29") (name "Net-(D19-C)") (class "Default")
      (node (ref "D19") (pin "2") (pinfunction "C_2") (pintype "unspecified"))
      (node (ref "D2") (pin "2") (pinfunction "C_2") (pintype "unspecified"))
      (node (ref "D29") (pin "2") (pinfunction "C_2") (pintype "unspecified"))
      (node (ref "D39") (pin "2") (pinfunction "C_2") (pintype "unspecified"))
      (node (ref "D49") (pin "2") (pinfunction "C_2") (pintype "unspecified"))
      (node (ref "D59") (pin "2") (pinfunction "C_2") (pintype "unspecified"))
      (node (ref "D69") (pin "2") (pinfunction "C_2") (pintype "unspecified"))
      (node (ref "D79") (pin "2") (pinfunction "C_2") (pintype "unspecified"))
      (node (ref "D89") (pin "2") (pinfunction "C_2") (pintype "unspecified"))
      (node (ref "GROUND7") (pin "2") (pinfunction "2_2") (pintype "unspecified"))
      (node (ref "SK2") (pin "13") (pinfunction "13_13") (pintype "unspecified"))
    )
    (net (code "30") (name "Net-(D20-A)") (class "Default")
      (node (ref "D20") (pin "1") (pinfunction "A_1") (pintype "unspecified"))
      (node (ref "U20") (pin "COL") (pinfunction "2_COL") (pintype "unspecified"))
    )
    (net (code "31") (name "Net-(D21-A)") (class "Default")
      (node (ref "D21") (pin "1") (pinfunction "A_1") (pintype "unspecified"))
      (node (ref "U21") (pin "COL") (pinfunction "2_COL") (pintype "unspecified"))
    )
    (net (code "32") (name "Net-(D22-A)") (class "Default")
      (node (ref "D22") (pin "1") (pinfunction "A_1") (pintype "unspecified"))
      (node (ref "U22") (pin "COL") (pinfunction "2_COL") (pintype "unspecified"))
    )
    (net (code "33") (name "Net-(D23-A)") (class "Default")
      (node (ref "D23") (pin "1") (pinfunction "A_1") (pintype "unspecified"))
      (node (ref "U23") (pin "COL") (pinfunction "2_COL") (pintype "unspecified"))
    )
    (net (code "34") (name "Net-(D24-A)") (class "Default")
      (node (ref "D24") (pin "1") (pinfunction "A_1") (pintype "unspecified"))
      (node (ref "U24") (pin "COL") (pinfunction "2_COL") (pintype "unspecified"))
    )
    (net (code "35") (name "Net-(D25-A)") (class "Default")
      (node (ref "D25") (pin "1") (pinfunction "A_1") (pintype "unspecified"))
      (node (ref "U25") (pin "COL") (pinfunction "2_COL") (pintype "unspecified"))
    )
    (net (code "36") (name "Net-(D26-A)") (class "Default")
      (node (ref "D26") (pin "1") (pinfunction "A_1") (pintype "unspecified"))
      (node (ref "U26") (pin "COL") (pinfunction "2_COL") (pintype "unspecified"))
    )
    (net (code "37") (name "Net-(D27-A)") (class "Default")
      (node (ref "D27") (pin "1") (pinfunction "A_1") (pintype "unspecified"))
      (node (ref "U27") (pin "COL") (pinfunction "2_COL") (pintype "unspecified"))
    )
    (net (code "38") (name "Net-(D28-A)") (class "Default")
      (node (ref "D28") (pin "1") (pinfunction "A_1") (pintype "unspecified"))
      (node (ref "U28") (pin "COL") (pinfunction "2_COL") (pintype "unspecified"))
    )
    (net (code "39") (name "Net-(D29-A)") (class "Default")
      (node (ref "D29") (pin "1") (pinfunction "A_1") (pintype "unspecified"))
      (node (ref "U29") (pin "COL") (pinfunction "2_COL") (pintype "unspecified"))
    )
    (net (code "40") (name "Net-(D30-A)") (class "Default")
      (node (ref "D30") (pin "1") (pinfunction "A_1") (pintype "unspecified"))
      (node (ref "U30") (pin "COL") (pinfunction "2_COL") (pintype "unspecified"))
    )
    (net (code "41") (name "Net-(D31-A)") (class "Default")
      (node (ref "D31") (pin "1") (pinfunction "A_1") (pintype "unspecified"))
      (node (ref "U31") (pin "COL") (pinfunction "2_COL") (pintype "unspecified"))
    )
    (net (code "42") (name "Net-(D32-A)") (class "Default")
      (node (ref "D32") (pin "1") (pinfunction "A_1") (pintype "unspecified"))
      (node (ref "U32") (pin "COL") (pinfunction "2_COL") (pintype "unspecified"))
    )
    (net (code "43") (name "Net-(D33-A)") (class "Default")
      (node (ref "D33") (pin "1") (pinfunction "A_1") (pintype "unspecified"))
      (node (ref "U33") (pin "COL") (pinfunction "2_COL") (pintype "unspecified"))
    )
    (net (code "44") (name "Net-(D34-A)") (class "Default")
      (node (ref "D34") (pin "1") (pinfunction "A_1") (pintype "unspecified"))
      (node (ref "U34") (pin "COL") (pinfunction "2_COL") (pintype "unspecified"))
    )
    (net (code "45") (name "Net-(D35-A)") (class "Default")
      (node (ref "D35") (pin "1") (pinfunction "A_1") (pintype "unspecified"))
      (node (ref "U35") (pin "COL") (pinfunction "2_COL") (pintype "unspecified"))
    )
    (net (code "46") (name "Net-(D36-A)") (class "Default")
      (node (ref "D36") (pin "1") (pinfunction "A_1") (pintype "unspecified"))
      (node (ref "U36") (pin "COL") (pinfunction "2_COL") (pintype "unspecified"))
    )
    (net (code "47") (name "Net-(D37-A)") (class "Default")
      (node (ref "D37") (pin "1") (pinfunction "A_1") (pintype "unspecified"))
      (node (ref "U37") (pin "COL") (pinfunction "2_COL") (pintype "unspecified"))
    )
    (net (code "48") (name "Net-(D38-A)") (class "Default")
      (node (ref "D38") (pin "1") (pinfunction "A_1") (pintype "unspecified"))
      (node (ref "U38") (pin "COL") (pinfunction "2_COL") (pintype "unspecified"))
    )
    (net (code "49") (name "Net-(D39-A)") (class "Default")
      (node (ref "D39") (pin "1") (pinfunction "A_1") (pintype "unspecified"))
      (node (ref "U39") (pin "COL") (pinfunction "2_COL") (pintype "unspecified"))
    )
    (net (code "50") (name "Net-(D40-A)") (class "Default")
      (node (ref "D40") (pin "1") (pinfunction "A_1") (pintype "unspecified"))
      (node (ref "U40") (pin "COL") (pinfunction "2_COL") (pintype "unspecified"))
    )
    (net (code "51") (name "Net-(D41-A)") (class "Default")
      (node (ref "D41") (pin "1") (pinfunction "A_1") (pintype "unspecified"))
      (node (ref "U41") (pin "COL") (pinfunction "2_COL") (pintype "unspecified"))
    )
    (net (code "52") (name "Net-(D42-A)") (class "Default")
      (node (ref "D42") (pin "1") (pinfunction "A_1") (pintype "unspecified"))
      (node (ref "U42") (pin "COL") (pinfunction "2_COL") (pintype "unspecified"))
    )
    (net (code "53") (name "Net-(D43-A)") (class "Default")
      (node (ref "D43") (pin "1") (pinfunction "A_1") (pintype "unspecified"))
      (node (ref "U43") (pin "COL") (pinfunction "2_COL") (pintype "unspecified"))
    )
    (net (code "54") (name "Net-(D44-A)") (class "Default")
      (node (ref "D44") (pin "1") (pinfunction "A_1") (pintype "unspecified"))
      (node (ref "U44") (pin "COL") (pinfunction "2_COL") (pintype "unspecified"))
    )
    (net (code "55") (name "Net-(D45-A)") (class "Default")
      (node (ref "D45") (pin "1") (pinfunction "A_1") (pintype "unspecified"))
      (node (ref "U45") (pin "COL") (pinfunction "2_COL") (pintype "unspecified"))
    )
    (net (code "56") (name "Net-(D46-A)") (class "Default")
      (node (ref "D46") (pin "1") (pinfunction "A_1") (pintype "unspecified"))
      (node (ref "U46") (pin "COL") (pinfunction "2_COL") (pintype "unspecified"))
    )
    (net (code "57") (name "Net-(D47-A)") (class "Default")
      (node (ref "D47") (pin "1") (pinfunction "A_1") (pintype "unspecified"))
      (node (ref "U47") (pin "COL") (pinfunction "2_COL") (pintype "unspecified"))
    )
    (net (code "58") (name "Net-(D48-A)") (class "Default")
      (node (ref "D48") (pin "1") (pinfunction "A_1") (pintype "unspecified"))
      (node (ref "U48") (pin "COL") (pinfunction "2_COL") (pintype "unspecified"))
    )
    (net (code "59") (name "Net-(D49-A)") (class "Default")
      (node (ref "D49") (pin "1") (pinfunction "A_1") (pintype "unspecified"))
      (node (ref "U49") (pin "COL") (pinfunction "2_COL") (pintype "unspecified"))
    )
    (net (code "60") (name "Net-(D50-A)") (class "Default")
      (node (ref "D50") (pin "1") (pinfunction "A_1") (pintype "unspecified"))
      (node (ref "U50") (pin "COL") (pinfunction "2_COL") (pintype "unspecified"))
    )
    (net (code "61") (name "Net-(D51-A)") (class "Default")
      (node (ref "D51") (pin "1") (pinfunction "A_1") (pintype "unspecified"))
      (node (ref "U51") (pin "COL") (pinfunction "2_COL") (pintype "unspecified"))
    )
    (net (code "62") (name "Net-(D52-A)") (class "Default")
      (node (ref "D52") (pin "1") (pinfunction "A_1") (pintype "unspecified"))
      (node (ref "U52") (pin "COL") (pinfunction "2_COL") (pintype "unspecified"))
    )
    (net (code "63") (name "Net-(D53-A)") (class "Default")
      (node (ref "D53") (pin "1") (pinfunction "A_1") (pintype "unspecified"))
      (node (ref "U53") (pin "COL") (pinfunction "2_COL") (pintype "unspecified"))
    )
    (net (code "64") (name "Net-(D54-A)") (class "Default")
      (node (ref "D54") (pin "1") (pinfunction "A_1") (pintype "unspecified"))
      (node (ref "U54") (pin "COL") (pinfunction "2_COL") (pintype "unspecified"))
    )
    (net (code "65") (name "Net-(D55-A)") (class "Default")
      (node (ref "D55") (pin "1") (pinfunction "A_1") (pintype "unspecified"))
      (node (ref "U55") (pin "COL") (pinfunction "2_COL") (pintype "unspecified"))
    )
    (net (code "66") (name "Net-(D56-A)") (class "Default")
      (node (ref "D56") (pin "1") (pinfunction "A_1") (pintype "unspecified"))
      (node (ref "U56") (pin "COL") (pinfunction "2_COL") (pintype "unspecified"))
    )
    (net (code "67") (name "Net-(D57-A)") (class "Default")
      (node (ref "D57") (pin "1") (pinfunction "A_1") (pintype "unspecified"))
      (node (ref "U57") (pin "COL") (pinfunction "2_COL") (pintype "unspecified"))
    )
    (net (code "68") (name "Net-(D58-A)") (class "Default")
      (node (ref "D58") (pin "1") (pinfunction "A_1") (pintype "unspecified"))
      (node (ref "U58") (pin "COL") (pinfunction "2_COL") (pintype "unspecified"))
    )
    (net (code "69") (name "Net-(D59-A)") (class "Default")
      (node (ref "D59") (pin "1") (pinfunction "A_1") (pintype "unspecified"))
      (node (ref "U59") (pin "COL") (pinfunction "2_COL") (pintype "unspecified"))
    )
    (net (code "70") (name "Net-(D60-A)") (class "Default")
      (node (ref "D60") (pin "1") (pinfunction "A_1") (pintype "unspecified"))
      (node (ref "U60") (pin "COL") (pinfunction "2_COL") (pintype "unspecified"))
    )
    (net (code "71") (name "Net-(D61-A)") (class "Default")
      (node (ref "D61") (pin "1") (pinfunction "A_1") (pintype "unspecified"))
      (node (ref "U61") (pin "COL") (pinfunction "2_COL") (pintype "unspecified"))
    )
    (net (code "72") (name "Net-(D62-A)") (class "Default")
      (node (ref "D62") (pin "1") (pinfunction "A_1") (pintype "unspecified"))
      (node (ref "U62") (pin "COL") (pinfunction "2_COL") (pintype "unspecified"))
    )
    (net (code "73") (name "Net-(D63-A)") (class "Default")
      (node (ref "D63") (pin "1") (pinfunction "A_1") (pintype "unspecified"))
      (node (ref "U63") (pin "COL") (pinfunction "2_COL") (pintype "unspecified"))
    )
    (net (code "74") (name "Net-(D64-A)") (class "Default")
      (node (ref "D64") (pin "1") (pinfunction "A_1") (pintype "unspecified"))
      (node (ref "U64") (pin "COL") (pinfunction "2_COL") (pintype "unspecified"))
    )
    (net (code "75") (name "Net-(D65-A)") (class "Default")
      (node (ref "D65") (pin "1") (pinfunction "A_1") (pintype "unspecified"))
      (node (ref "U65") (pin "COL") (pinfunction "2_COL") (pintype "unspecified"))
    )
    (net (code "76") (name "Net-(D66-A)") (class "Default")
      (node (ref "D66") (pin "1") (pinfunction "A_1") (pintype "unspecified"))
      (node (ref "U66") (pin "COL") (pinfunction "2_COL") (pintype "unspecified"))
    )
    (net (code "77") (name "Net-(D67-A)") (class "Default")
      (node (ref "D67") (pin "1") (pinfunction "A_1") (pintype "unspecified"))
      (node (ref "U67") (pin "COL") (pinfunction "2_COL") (pintype "unspecified"))
    )
    (net (code "78") (name "Net-(D68-A)") (class "Default")
      (node (ref "D68") (pin "1") (pinfunction "A_1") (pintype "unspecified"))
      (node (ref "U68") (pin "COL") (pinfunction "2_COL") (pintype "unspecified"))
    )
    (net (code "79") (name "Net-(D69-A)") (class "Default")
      (node (ref "D69") (pin "1") (pinfunction "A_1") (pintype "unspecified"))
      (node (ref "U69") (pin "COL") (pinfunction "2_COL") (pintype "unspecified"))
    )
    (net (code "80") (name "Net-(D70-A)") (class "Default")
      (node (ref "D70") (pin "1") (pinfunction "A_1") (pintype "unspecified"))
      (node (ref "U70") (pin "COL") (pinfunction "2_COL") (pintype "unspecified"))
    )
    (net (code "81") (name "Net-(D71-A)") (class "Default")
      (node (ref "D71") (pin "1") (pinfunction "A_1") (pintype "unspecified"))
      (node (ref "U71") (pin "COL") (pinfunction "2_COL") (pintype "unspecified"))
    )
    (net (code "82") (name "Net-(D72-A)") (class "Default")
      (node (ref "D72") (pin "1") (pinfunction "A_1") (pintype "unspecified"))
      (node (ref "U72") (pin "COL") (pinfunction "2_COL") (pintype "unspecified"))
    )
    (net (code "83") (name "Net-(D73-A)") (class "Default")
      (node (ref "D73") (pin "1") (pinfunction "A_1") (pintype "unspecified"))
      (node (ref "U73") (pin "COL") (pinfunction "2_COL") (pintype "unspecified"))
    )
    (net (code "84") (name "Net-(D74-A)") (class "Default")
      (node (ref "D74") (pin "1") (pinfunction "A_1") (pintype "unspecified"))
      (node (ref "U74") (pin "COL") (pinfunction "2_COL") (pintype "unspecified"))
    )
    (net (code "85") (name "Net-(D75-A)") (class "Default")
      (node (ref "D75") (pin "1") (pinfunction "A_1") (pintype "unspecified"))
      (node (ref "U75") (pin "COL") (pinfunction "2_COL") (pintype "unspecified"))
    )
    (net (code "86") (name "Net-(D76-A)") (class "Default")
      (node (ref "D76") (pin "1") (pinfunction "A_1") (pintype "unspecified"))
      (node (ref "U76") (pin "COL") (pinfunction "2_COL") (pintype "unspecified"))
    )
    (net (code "87") (name "Net-(D77-A)") (class "Default")
      (node (ref "D77") (pin "1") (pinfunction "A_1") (pintype "unspecified"))
      (node (ref "U77") (pin "COL") (pinfunction "2_COL") (pintype "unspecified"))
    )
    (net (code "88") (name "Net-(D78-A)") (class "Default")
      (node (ref "D78") (pin "1") (pinfunction "A_1") (pintype "unspecified"))
      (node (ref "U78") (pin "COL") (pinfunction "2_COL") (pintype "unspecified"))
    )
    (net (code "89") (name "Net-(D79-A)") (class "Default")
      (node (ref "D79") (pin "1") (pinfunction "A_1") (pintype "unspecified"))
      (node (ref "U79") (pin "COL") (pinfunction "2_COL") (pintype "unspecified"))
    )
    (net (code "90") (name "Net-(D80-A)") (class "Default")
      (node (ref "D80") (pin "1") (pinfunction "A_1") (pintype "unspecified"))
      (node (ref "U80") (pin "COL") (pinfunction "2_COL") (pintype "unspecified"))
    )
    (net (code "91") (name "Net-(D81-A)") (class "Default")
      (node (ref "D81") (pin "1") (pinfunction "A_1") (pintype "unspecified"))
      (node (ref "U81") (pin "COL") (pinfunction "2_COL") (pintype "unspecified"))
    )
    (net (code "92") (name "Net-(D82-A)") (class "Default")
      (node (ref "D82") (pin "1") (pinfunction "A_1") (pintype "unspecified"))
      (node (ref "U82") (pin "COL") (pinfunction "2_COL") (pintype "unspecified"))
    )
    (net (code "93") (name "Net-(D83-A)") (class "Default")
      (node (ref "D83") (pin "1") (pinfunction "A_1") (pintype "unspecified"))
      (node (ref "U83") (pin "COL") (pinfunction "2_COL") (pintype "unspecified"))
    )
    (net (code "94") (name "Net-(D84-A)") (class "Default")
      (node (ref "D84") (pin "1") (pinfunction "A_1") (pintype "unspecified"))
      (node (ref "U84") (pin "COL") (pinfunction "2_COL") (pintype "unspecified"))
    )
    (net (code "95") (name "Net-(D85-A)") (class "Default")
      (node (ref "D85") (pin "1") (pinfunction "A_1") (pintype "unspecified"))
      (node (ref "U85") (pin "COL") (pinfunction "2_COL") (pintype "unspecified"))
    )
    (net (code "96") (name "Net-(D86-A)") (class "Default")
      (node (ref "D86") (pin "1") (pinfunction "A_1") (pintype "unspecified"))
      (node (ref "U86") (pin "COL") (pinfunction "2_COL") (pintype "unspecified"))
    )
    (net (code "97") (name "Net-(D87-A)") (class "Default")
      (node (ref "D87") (pin "1") (pinfunction "A_1") (pintype "unspecified"))
      (node (ref "U87") (pin "COL") (pinfunction "2_COL") (pintype "unspecified"))
    )
    (net (code "98") (name "Net-(D88-A)") (class "Default")
      (node (ref "D88") (pin "1") (pinfunction "A_1") (pintype "unspecified"))
      (node (ref "U88") (pin "COL") (pinfunction "2_COL") (pintype "unspecified"))
    )
    (net (code "99") (name "Net-(D89-A)") (class "Default")
      (node (ref "D89") (pin "1") (pinfunction "A_1") (pintype "unspecified"))
      (node (ref "U89") (pin "COL") (pinfunction "2_COL") (pintype "unspecified"))
    )
    (net (code "100") (name "Net-(D90-A)") (class "Default")
      (node (ref "D90") (pin "1") (pinfunction "A_1") (pintype "unspecified"))
      (node (ref "U90") (pin "COL") (pinfunction "2_COL") (pintype "unspecified"))
    )
    (net (code "101") (name "Net-(LED1-Pad2)") (class "Default")
      (node (ref "LED1") (pin "2") (pinfunction "2_2") (pintype "unspecified"))
      (node (ref "LED2") (pin "2") (pinfunction "2_2") (pintype "unspecified"))
      (node (ref "LED3") (pin "2") (pinfunction "2_2") (pintype "unspecified"))
      (node (ref "R4") (pin "2") (pinfunction "2_2") (pintype "unspecified"))
    )
    (net (code "102") (name "Net-(R1-Pad2)") (class "Default")
      (node (ref "R1") (pin "2") (pinfunction "2_2") (pintype "unspecified"))
      (node (ref "SK2") (pin "1") (pinfunction "1_1") (pintype "unspecified"))
      (node (ref "SW1") (pin "3") (pinfunction "3_3") (pintype "unspecified"))
    )
    (net (code "103") (name "Net-(R2-Pad2)") (class "Default")
      (node (ref "R2") (pin "2") (pinfunction "2_2") (pintype "unspecified"))
      (node (ref "SK2") (pin "3") (pinfunction "3_3") (pintype "unspecified"))
      (node (ref "SW1") (pin "1") (pinfunction "1_1") (pintype "unspecified"))
    )
    (net (code "104") (name "Net-(R4-Pad1)") (class "Default")
      (node (ref "R4") (pin "1") (pinfunction "1_1") (pintype "unspecified"))
      (node (ref "U96") (pin "34") (pinfunction "GND_34") (pintype "unspecified"))
    )
    (net (code "105") (name "Net-(R6-Pad2)") (class "Default")
      (node (ref "R6") (pin "2") (pinfunction "2_2") (pintype "unspecified"))
      (node (ref "S2") (pin "A") (pinfunction "A_A") (pintype "bidirectional"))
      (node (ref "SK2") (pin "10") (pinfunction "10_10") (pintype "unspecified"))
    )
    (net (code "106") (name "Net-(R7-Pad2)") (class "Default")
      (node (ref "R7") (pin "2") (pinfunction "2_2") (pintype "unspecified"))
      (node (ref "S2") (pin "B") (pinfunction "B_B") (pintype "bidirectional"))
      (node (ref "SK2") (pin "8") (pinfunction "8_8") (pintype "unspecified"))
    )
    (net (code "107") (name "Net-(S1-H)") (class "Default")
      (node (ref "S1") (pin "H2") (pinfunction "H_H2") (pintype "bidirectional"))
      (node (ref "U92") (pin "7") (pinfunction "7_7") (pintype "unspecified"))
    )
    (net (code "108") (name "Net-(S1-H+)") (class "Default")
      (node (ref "R6") (pin "1") (pinfunction "1_1") (pintype "unspecified"))
      (node (ref "R7") (pin "1") (pinfunction "1_1") (pintype "unspecified"))
      (node (ref "S1") (pin "B2A") (pinfunction "SEL-_B2A") (pintype "bidirectional"))
      (node (ref "S1") (pin "H1") (pinfunction "H+_H1") (pintype "bidirectional"))
      (node (ref "S1") (pin "V1") (pinfunction "V+_V1") (pintype "bidirectional"))
      (node (ref "S2") (pin "5") (pinfunction "+_5") (pintype "bidirectional"))
      (node (ref "SDA") (pin "2") (pinfunction "2_2") (pintype "unspecified"))
      (node (ref "SDL") (pin "2") (pinfunction "2_2") (pintype "unspecified"))
      (node (ref "SK1") (pin "17") (pinfunction "Vdd_17") (pintype "unspecified"))
      (node (ref "SK1") (pin "22") (pinfunction "RT_22") (pintype "unspecified"))
      (node (ref "SK2") (pin "17") (pinfunction "Vdd_17") (pintype "unspecified"))
      (node (ref "SK2") (pin "22") (pinfunction "RT_22") (pintype "unspecified"))
      (node (ref "SK2") (pin "24") (pinfunction "A2_24") (pintype "unspecified"))
      (node (ref "SW1") (pin "2") (pinfunction "2_2") (pintype "unspecified"))
      (node (ref "U91") (pin "1") (pinfunction "VCC_1") (pintype "unspecified"))
      (node (ref "U92") (pin "15") (pinfunction "15_15") (pintype "unspecified"))
      (node (ref "U92") (pin "16") (pinfunction "16_16") (pintype "unspecified"))
      (node (ref "U96") (pin "1") (pinfunction "3V3_1") (pintype "unspecified"))
      (node (ref "VR1") (pin "P$3") (pinfunction "A_P$3") (pintype "bidirectional"))
      (node (ref "VR2") (pin "P$3") (pinfunction "A_P$3") (pintype "bidirectional"))
    )
    (net (code "109") (name "Net-(S1-H-)") (class "Default")
      (node (ref "GROUND") (pin "1") (pinfunction "1_1") (pintype "unspecified"))
      (node (ref "GROUND1") (pin "1") (pinfunction "1_1") (pintype "unspecified"))
      (node (ref "GROUND2") (pin "1") (pinfunction "1_1") (pintype "unspecified"))
      (node (ref "GROUND3") (pin "1") (pinfunction "1_1") (pintype "unspecified"))
      (node (ref "GROUND4") (pin "1") (pinfunction "1_1") (pintype "unspecified"))
      (node (ref "GROUND5") (pin "1") (pinfunction "1_1") (pintype "unspecified"))
      (node (ref "GROUND6") (pin "1") (pinfunction "1_1") (pintype "unspecified"))
      (node (ref "GROUND7") (pin "1") (pinfunction "1_1") (pintype "unspecified"))
      (node (ref "GROUND8") (pin "1") (pinfunction "1_1") (pintype "unspecified"))
      (node (ref "GROUND9") (pin "1") (pinfunction "1_1") (pintype "unspecified"))
      (node (ref "R1") (pin "1") (pinfunction "1_1") (pintype "unspecified"))
      (node (ref "R2") (pin "1") (pinfunction "1_1") (pintype "unspecified"))
      (node (ref "R3") (pin "1") (pinfunction "1_1") (pintype "unspecified"))
      (node (ref "R5") (pin "1") (pinfunction "1_1") (pintype "unspecified"))
      (node (ref "S1") (pin "H3") (pinfunction "H-_H3") (pintype "bidirectional"))
      (node (ref "S1") (pin "V3") (pinfunction "V-_V3") (pintype "bidirectional"))
      (node (ref "S2") (pin "C") (pinfunction "C_C") (pintype "bidirectional"))
      (node (ref "SK1") (pin "19") (pinfunction "Vss_19") (pintype "unspecified"))
      (node (ref "SK1") (pin "24") (pinfunction "A2_24") (pintype "unspecified"))
      (node (ref "SK1") (pin "26") (pinfunction "A1_26") (pintype "unspecified"))
      (node (ref "SK1") (pin "28") (pinfunction "A0_28") (pintype "unspecified"))
      (node (ref "SK2") (pin "19") (pinfunction "Vss_19") (pintype "unspecified"))
      (node (ref "SK2") (pin "26") (pinfunction "A1_26") (pintype "unspecified"))
      (node (ref "SK2") (pin "28") (pinfunction "A0_28") (pintype "unspecified"))
      (node (ref "U91") (pin "2") (pinfunction "GND_2") (pintype "unspecified"))
      (node (ref "U91") (pin "7") (pinfunction "DC_7") (pintype "unspecified"))
      (node (ref "U92") (pin "14") (pinfunction "14_14") (pintype "unspecified"))
      (node (ref "U92") (pin "9") (pinfunction "9_9") (pintype "unspecified"))
      (node (ref "U96") (pin "9") (pinfunction "GND_9") (pintype "unspecified"))
      (node (ref "VR1") (pin "P$1") (pinfunction "E_P$1") (pintype "bidirectional"))
      (node (ref "VR2") (pin "P$1") (pinfunction "E_P$1") (pintype "bidirectional"))
    )
    (net (code "110") (name "Net-(S1-SEL+)") (class "Default")
      (node (ref "R3") (pin "2") (pinfunction "2_2") (pintype "unspecified"))
      (node (ref "S1") (pin "B1A") (pinfunction "SEL+_B1A") (pintype "bidirectional"))
      (node (ref "SK1") (pin "1") (pinfunction "1_1") (pintype "unspecified"))
    )
    (net (code "111") (name "Net-(S1-V)") (class "Default")
      (node (ref "S1") (pin "V2") (pinfunction "V_V2") (pintype "bidirectional"))
      (node (ref "U92") (pin "8") (pinfunction "8_8") (pintype "unspecified"))
    )
    (net (code "112") (name "Net-(S2--B)") (class "Default")
      (node (ref "S2") (pin "4") (pinfunction "-B_4") (pintype "bidirectional"))
      (node (ref "SK2") (pin "12") (pinfunction "12_12") (pintype "unspecified"))
    )
    (net (code "113") (name "Net-(S2--G)") (class "Default")
      (node (ref "S2") (pin "2") (pinfunction "-G_2") (pintype "bidirectional"))
      (node (ref "SK2") (pin "11") (pinfunction "11_11") (pintype "unspecified"))
    )
    (net (code "114") (name "Net-(S2--R)") (class "Default")
      (node (ref "S2") (pin "1") (pinfunction "-R_1") (pintype "bidirectional"))
      (node (ref "SK2") (pin "16") (pinfunction "16_16") (pintype "unspecified"))
    )
    (net (code "115") (name "Net-(S2-SW)") (class "Default")
      (node (ref "R5") (pin "2") (pinfunction "2_2") (pintype "unspecified"))
      (node (ref "S2") (pin "3") (pinfunction "SW_3") (pintype "bidirectional"))
      (node (ref "SK2") (pin "14") (pinfunction "14_14") (pintype "unspecified"))
    )
    (net (code "116") (name "Net-(SK1-SDA)") (class "Default")
      (node (ref "SDA") (pin "1") (pinfunction "1_1") (pintype "unspecified"))
      (node (ref "SK1") (pin "25") (pinfunction "SDA_25") (pintype "unspecified"))
      (node (ref "SK2") (pin "25") (pinfunction "SDA_25") (pintype "unspecified"))
      (node (ref "U91") (pin "4") (pinfunction "DIN_4") (pintype "unspecified"))
      (node (ref "U96") (pin "11") (pinfunction "GPIO17_11") (pintype "unspecified"))
    )
    (net (code "117") (name "Net-(SK1-SDL)") (class "Default")
      (node (ref "SDL") (pin "1") (pinfunction "1_1") (pintype "unspecified"))
      (node (ref "SK1") (pin "23") (pinfunction "SDL_23") (pintype "unspecified"))
      (node (ref "SK2") (pin "23") (pinfunction "SDL_23") (pintype "unspecified"))
      (node (ref "U91") (pin "5") (pinfunction "CLK_5") (pintype "unspecified"))
      (node (ref "U96") (pin "13") (pinfunction "GPIO27_13") (pintype "unspecified"))
    )
    (net (code "118") (name "Net-(U1-1)") (class "Default")
      (node (ref "SK1") (pin "5") (pinfunction "5_5") (pintype "unspecified"))
      (node (ref "U1") (pin "ROW") (pinfunction "1_ROW") (pintype "unspecified"))
      (node (ref "U10") (pin "ROW") (pinfunction "1_ROW") (pintype "unspecified"))
      (node (ref "U2") (pin "ROW") (pinfunction "1_ROW") (pintype "unspecified"))
      (node (ref "U3") (pin "ROW") (pinfunction "1_ROW") (pintype "unspecified"))
      (node (ref "U4") (pin "ROW") (pinfunction "1_ROW") (pintype "unspecified"))
      (node (ref "U5") (pin "ROW") (pinfunction "1_ROW") (pintype "unspecified"))
      (node (ref "U6") (pin "ROW") (pinfunction "1_ROW") (pintype "unspecified"))
      (node (ref "U7") (pin "ROW") (pinfunction "1_ROW") (pintype "unspecified"))
      (node (ref "U8") (pin "ROW") (pinfunction "1_ROW") (pintype "unspecified"))
      (node (ref "U9") (pin "ROW") (pinfunction "1_ROW") (pintype "unspecified"))
    )
    (net (code "119") (name "Net-(U11-1)") (class "Default")
      (node (ref "SK1") (pin "7") (pinfunction "7_7") (pintype "unspecified"))
      (node (ref "U11") (pin "ROW") (pinfunction "1_ROW") (pintype "unspecified"))
      (node (ref "U12") (pin "ROW") (pinfunction "1_ROW") (pintype "unspecified"))
      (node (ref "U13") (pin "ROW") (pinfunction "1_ROW") (pintype "unspecified"))
      (node (ref "U14") (pin "ROW") (pinfunction "1_ROW") (pintype "unspecified"))
      (node (ref "U15") (pin "ROW") (pinfunction "1_ROW") (pintype "unspecified"))
      (node (ref "U16") (pin "ROW") (pinfunction "1_ROW") (pintype "unspecified"))
      (node (ref "U17") (pin "ROW") (pinfunction "1_ROW") (pintype "unspecified"))
      (node (ref "U18") (pin "ROW") (pinfunction "1_ROW") (pintype "unspecified"))
      (node (ref "U19") (pin "ROW") (pinfunction "1_ROW") (pintype "unspecified"))
      (node (ref "U20") (pin "ROW") (pinfunction "1_ROW") (pintype "unspecified"))
    )
    (net (code "120") (name "Net-(U21-1)") (class "Default")
      (node (ref "SK1") (pin "9") (pinfunction "9_9") (pintype "unspecified"))
      (node (ref "U21") (pin "ROW") (pinfunction "1_ROW") (pintype "unspecified"))
      (node (ref "U22") (pin "ROW") (pinfunction "1_ROW") (pintype "unspecified"))
      (node (ref "U23") (pin "ROW") (pinfunction "1_ROW") (pintype "unspecified"))
      (node (ref "U24") (pin "ROW") (pinfunction "1_ROW") (pintype "unspecified"))
      (node (ref "U25") (pin "ROW") (pinfunction "1_ROW") (pintype "unspecified"))
      (node (ref "U26") (pin "ROW") (pinfunction "1_ROW") (pintype "unspecified"))
      (node (ref "U27") (pin "ROW") (pinfunction "1_ROW") (pintype "unspecified"))
      (node (ref "U28") (pin "ROW") (pinfunction "1_ROW") (pintype "unspecified"))
      (node (ref "U29") (pin "ROW") (pinfunction "1_ROW") (pintype "unspecified"))
      (node (ref "U30") (pin "ROW") (pinfunction "1_ROW") (pintype "unspecified"))
    )
    (net (code "121") (name "Net-(U31-1)") (class "Default")
      (node (ref "SK1") (pin "11") (pinfunction "11_11") (pintype "unspecified"))
      (node (ref "U31") (pin "ROW") (pinfunction "1_ROW") (pintype "unspecified"))
      (node (ref "U32") (pin "ROW") (pinfunction "1_ROW") (pintype "unspecified"))
      (node (ref "U33") (pin "ROW") (pinfunction "1_ROW") (pintype "unspecified"))
      (node (ref "U34") (pin "ROW") (pinfunction "1_ROW") (pintype "unspecified"))
      (node (ref "U35") (pin "ROW") (pinfunction "1_ROW") (pintype "unspecified"))
      (node (ref "U36") (pin "ROW") (pinfunction "1_ROW") (pintype "unspecified"))
      (node (ref "U37") (pin "ROW") (pinfunction "1_ROW") (pintype "unspecified"))
      (node (ref "U38") (pin "ROW") (pinfunction "1_ROW") (pintype "unspecified"))
      (node (ref "U39") (pin "ROW") (pinfunction "1_ROW") (pintype "unspecified"))
      (node (ref "U40") (pin "ROW") (pinfunction "1_ROW") (pintype "unspecified"))
    )
    (net (code "122") (name "Net-(U41-1)") (class "Default")
      (node (ref "SK1") (pin "13") (pinfunction "13_13") (pintype "unspecified"))
      (node (ref "U41") (pin "ROW") (pinfunction "1_ROW") (pintype "unspecified"))
      (node (ref "U42") (pin "ROW") (pinfunction "1_ROW") (pintype "unspecified"))
      (node (ref "U43") (pin "ROW") (pinfunction "1_ROW") (pintype "unspecified"))
      (node (ref "U44") (pin "ROW") (pinfunction "1_ROW") (pintype "unspecified"))
      (node (ref "U45") (pin "ROW") (pinfunction "1_ROW") (pintype "unspecified"))
      (node (ref "U46") (pin "ROW") (pinfunction "1_ROW") (pintype "unspecified"))
      (node (ref "U47") (pin "ROW") (pinfunction "1_ROW") (pintype "unspecified"))
      (node (ref "U48") (pin "ROW") (pinfunction "1_ROW") (pintype "unspecified"))
      (node (ref "U49") (pin "ROW") (pinfunction "1_ROW") (pintype "unspecified"))
      (node (ref "U50") (pin "ROW") (pinfunction "1_ROW") (pintype "unspecified"))
    )
    (net (code "123") (name "Net-(U51-1)") (class "Default")
      (node (ref "SK1") (pin "15") (pinfunction "15_15") (pintype "unspecified"))
      (node (ref "U51") (pin "ROW") (pinfunction "1_ROW") (pintype "unspecified"))
      (node (ref "U52") (pin "ROW") (pinfunction "1_ROW") (pintype "unspecified"))
      (node (ref "U53") (pin "ROW") (pinfunction "1_ROW") (pintype "unspecified"))
      (node (ref "U54") (pin "ROW") (pinfunction "1_ROW") (pintype "unspecified"))
      (node (ref "U55") (pin "ROW") (pinfunction "1_ROW") (pintype "unspecified"))
      (node (ref "U56") (pin "ROW") (pinfunction "1_ROW") (pintype "unspecified"))
      (node (ref "U57") (pin "ROW") (pinfunction "1_ROW") (pintype "unspecified"))
      (node (ref "U58") (pin "ROW") (pinfunction "1_ROW") (pintype "unspecified"))
      (node (ref "U59") (pin "ROW") (pinfunction "1_ROW") (pintype "unspecified"))
      (node (ref "U60") (pin "ROW") (pinfunction "1_ROW") (pintype "unspecified"))
    )
    (net (code "124") (name "Net-(U61-1)") (class "Default")
      (node (ref "SK2") (pin "6") (pinfunction "6_6") (pintype "unspecified"))
      (node (ref "U61") (pin "ROW") (pinfunction "1_ROW") (pintype "unspecified"))
      (node (ref "U62") (pin "ROW") (pinfunction "1_ROW") (pintype "unspecified"))
      (node (ref "U63") (pin "ROW") (pinfunction "1_ROW") (pintype "unspecified"))
      (node (ref "U64") (pin "ROW") (pinfunction "1_ROW") (pintype "unspecified"))
      (node (ref "U65") (pin "ROW") (pinfunction "1_ROW") (pintype "unspecified"))
      (node (ref "U66") (pin "ROW") (pinfunction "1_ROW") (pintype "unspecified"))
      (node (ref "U67") (pin "ROW") (pinfunction "1_ROW") (pintype "unspecified"))
      (node (ref "U68") (pin "ROW") (pinfunction "1_ROW") (pintype "unspecified"))
      (node (ref "U69") (pin "ROW") (pinfunction "1_ROW") (pintype "unspecified"))
      (node (ref "U70") (pin "ROW") (pinfunction "1_ROW") (pintype "unspecified"))
    )
    (net (code "125") (name "Net-(U71-1)") (class "Default")
      (node (ref "SK2") (pin "4") (pinfunction "4_4") (pintype "unspecified"))
      (node (ref "U71") (pin "ROW") (pinfunction "1_ROW") (pintype "unspecified"))
      (node (ref "U72") (pin "ROW") (pinfunction "1_ROW") (pintype "unspecified"))
      (node (ref "U73") (pin "ROW") (pinfunction "1_ROW") (pintype "unspecified"))
      (node (ref "U74") (pin "ROW") (pinfunction "1_ROW") (pintype "unspecified"))
      (node (ref "U75") (pin "ROW") (pinfunction "1_ROW") (pintype "unspecified"))
      (node (ref "U76") (pin "ROW") (pinfunction "1_ROW") (pintype "unspecified"))
      (node (ref "U77") (pin "ROW") (pinfunction "1_ROW") (pintype "unspecified"))
      (node (ref "U78") (pin "ROW") (pinfunction "1_ROW") (pintype "unspecified"))
      (node (ref "U79") (pin "ROW") (pinfunction "1_ROW") (pintype "unspecified"))
      (node (ref "U80") (pin "ROW") (pinfunction "1_ROW") (pintype "unspecified"))
    )
    (net (code "126") (name "Net-(U81-1)") (class "Default")
      (node (ref "SK2") (pin "2") (pinfunction "2_2") (pintype "unspecified"))
      (node (ref "U81") (pin "ROW") (pinfunction "1_ROW") (pintype "unspecified"))
      (node (ref "U82") (pin "ROW") (pinfunction "1_ROW") (pintype "unspecified"))
      (node (ref "U83") (pin "ROW") (pinfunction "1_ROW") (pintype "unspecified"))
      (node (ref "U84") (pin "ROW") (pinfunction "1_ROW") (pintype "unspecified"))
      (node (ref "U85") (pin "ROW") (pinfunction "1_ROW") (pintype "unspecified"))
      (node (ref "U86") (pin "ROW") (pinfunction "1_ROW") (pintype "unspecified"))
      (node (ref "U87") (pin "ROW") (pinfunction "1_ROW") (pintype "unspecified"))
      (node (ref "U88") (pin "ROW") (pinfunction "1_ROW") (pintype "unspecified"))
      (node (ref "U89") (pin "ROW") (pinfunction "1_ROW") (pintype "unspecified"))
      (node (ref "U90") (pin "ROW") (pinfunction "1_ROW") (pintype "unspecified"))
    )
    (net (code "127") (name "Net-(U91-RST)") (class "Default")
      (node (ref "U91") (pin "8") (pinfunction "RST_8") (pintype "unspecified"))
      (node (ref "U96") (pin "8") (pinfunction "GPIO14_8") (pintype "unspecified"))
    )
    (net (code "128") (name "Net-(U96-GPIO8)") (class "Default")
      (node (ref "U92") (pin "10") (pinfunction "10_10") (pintype "unspecified"))
      (node (ref "U96") (pin "24") (pinfunction "GPIO8_24") (pintype "unspecified"))
    )
    (net (code "129") (name "Net-(U96-GPIO9)") (class "Default")
      (node (ref "U92") (pin "12") (pinfunction "12_12") (pintype "unspecified"))
      (node (ref "U96") (pin "21") (pinfunction "GPIO9_21") (pintype "unspecified"))
    )
    (net (code "130") (name "Net-(U96-GPIO10)") (class "Default")
      (node (ref "U92") (pin "11") (pinfunction "11_11") (pintype "unspecified"))
      (node (ref "U96") (pin "19") (pinfunction "GPIO10_19") (pintype "unspecified"))
    )
    (net (code "131") (name "Net-(U96-GPIO11)") (class "Default")
      (node (ref "U92") (pin "13") (pinfunction "13_13") (pintype "unspecified"))
      (node (ref "U96") (pin "23") (pinfunction "GPIO11_23") (pintype "unspecified"))
    )
    (net (code "132") (name "Net-(U96-GPIO16)") (class "Default")
      (node (ref "LED1") (pin "1") (pinfunction "1_1") (pintype "unspecified"))
      (node (ref "U96") (pin "36") (pinfunction "GPIO16_36") (pintype "unspecified"))
    )
    (net (code "133") (name "Net-(U96-GPIO20)") (class "Default")
      (node (ref "LED2") (pin "1") (pinfunction "1_1") (pintype "unspecified"))
      (node (ref "U96") (pin "38") (pinfunction "GPIO20_38") (pintype "unspecified"))
    )
    (net (code "134") (name "Net-(U96-GPIO21)") (class "Default")
      (node (ref "LED3") (pin "1") (pinfunction "1_1") (pintype "unspecified"))
      (node (ref "U96") (pin "40") (pinfunction "GPIO21_40") (pintype "unspecified"))
    )
    (net (code "135") (name "Net-(VR1-S)") (class "Default")
      (node (ref "U92") (pin "1") (pinfunction "1_1") (pintype "unspecified"))
      (node (ref "VR1") (pin "P$2") (pinfunction "S_P$2") (pintype "bidirectional"))
    )
    (net (code "136") (name "Net-(VR2-S)") (class "Default")
      (node (ref "U92") (pin "2") (pinfunction "2_2") (pintype "unspecified"))
      (node (ref "VR2") (pin "P$2") (pinfunction "S_P$2") (pintype "bidirectional"))
    )
    (net (code "137") (name "unconnected-(SK1-IA-Pad18)") (class "Default")
      (node (ref "SK1") (pin "18") (pinfunction "IA_18") (pintype "unspecified"))
    )
    (net (code "138") (name "unconnected-(SK1-IB-Pad20)") (class "Default")
      (node (ref "SK1") (pin "20") (pinfunction "IB_20") (pintype "unspecified"))
    )
    (net (code "139") (name "unconnected-(SK1-NC-Pad21)") (class "Default")
      (node (ref "SK1") (pin "21") (pinfunction "NC_21") (pintype "unspecified"))
    )
    (net (code "140") (name "unconnected-(SK1-NC-Pad27)") (class "Default")
      (node (ref "SK1") (pin "27") (pinfunction "NC_27") (pintype "unspecified"))
    )
    (net (code "141") (name "unconnected-(SK1-Pad3)") (class "Default")
      (node (ref "SK1") (pin "3") (pinfunction "3_3") (pintype "unspecified"))
    )
    (net (code "142") (name "unconnected-(SK2-IA-Pad18)") (class "Default")
      (node (ref "SK2") (pin "18") (pinfunction "IA_18") (pintype "unspecified"))
    )
    (net (code "143") (name "unconnected-(SK2-IB-Pad20)") (class "Default")
      (node (ref "SK2") (pin "20") (pinfunction "IB_20") (pintype "unspecified"))
    )
    (net (code "144") (name "unconnected-(SK2-NC-Pad21)") (class "Default")
      (node (ref "SK2") (pin "21") (pinfunction "NC_21") (pintype "unspecified"))
    )
    (net (code "145") (name "unconnected-(SK2-NC-Pad27)") (class "Default")
      (node (ref "SK2") (pin "27") (pinfunction "NC_27") (pintype "unspecified"))
    )
    (net (code "146") (name "unconnected-(SK2-Pad5)") (class "Default")
      (node (ref "SK2") (pin "5") (pinfunction "5_5") (pintype "unspecified"))
    )
    (net (code "147") (name "unconnected-(SK2-Pad7)") (class "Default")
      (node (ref "SK2") (pin "7") (pinfunction "7_7") (pintype "unspecified"))
    )
    (net (code "148") (name "unconnected-(SK2-Pad9)") (class "Default")
      (node (ref "SK2") (pin "9") (pinfunction "9_9") (pintype "unspecified"))
    )
    (net (code "149") (name "unconnected-(U91-CS-Pad6)") (class "Default")
      (node (ref "U91") (pin "6") (pinfunction "CS_6") (pintype "unspecified"))
    )
    (net (code "150") (name "unconnected-(U91-NC-Pad3)") (class "Default")
      (node (ref "U91") (pin "3") (pinfunction "NC_3") (pintype "unspecified"))
    )
    (net (code "151") (name "unconnected-(U92-Pad3)") (class "Default")
      (node (ref "U92") (pin "3") (pinfunction "3_3") (pintype "unspecified"))
    )
    (net (code "152") (name "unconnected-(U92-Pad4)") (class "Default")
      (node (ref "U92") (pin "4") (pinfunction "4_4") (pintype "unspecified"))
    )
    (net (code "153") (name "unconnected-(U92-Pad5)") (class "Default")
      (node (ref "U92") (pin "5") (pinfunction "5_5") (pintype "unspecified"))
    )
    (net (code "154") (name "unconnected-(U92-Pad6)") (class "Default")
      (node (ref "U92") (pin "6") (pinfunction "6_6") (pintype "unspecified"))
    )
    (net (code "155") (name "unconnected-(U96-3V3-Pad17)") (class "Default")
      (node (ref "U96") (pin "17") (pinfunction "3V3_17") (pintype "unspecified"))
    )
    (net (code "156") (name "unconnected-(U96-5V-Pad2)") (class "Default")
      (node (ref "U96") (pin "2") (pinfunction "5V_2") (pintype "unspecified"))
    )
    (net (code "157") (name "unconnected-(U96-5V-Pad4)") (class "Default")
      (node (ref "U96") (pin "4") (pinfunction "5V_4") (pintype "unspecified"))
    )
    (net (code "158") (name "unconnected-(U96-GND-Pad6)") (class "Default")
      (node (ref "U96") (pin "6") (pinfunction "GND_6") (pintype "unspecified"))
    )
    (net (code "159") (name "unconnected-(U96-GND-Pad14)") (class "Default")
      (node (ref "U96") (pin "14") (pinfunction "GND_14") (pintype "unspecified"))
    )
    (net (code "160") (name "unconnected-(U96-GND-Pad20)") (class "Default")
      (node (ref "U96") (pin "20") (pinfunction "GND_20") (pintype "unspecified"))
    )
    (net (code "161") (name "unconnected-(U96-GND-Pad25)") (class "Default")
      (node (ref "U96") (pin "25") (pinfunction "GND_25") (pintype "unspecified"))
    )
    (net (code "162") (name "unconnected-(U96-GND-Pad30)") (class "Default")
      (node (ref "U96") (pin "30") (pinfunction "GND_30") (pintype "unspecified"))
    )
    (net (code "163") (name "unconnected-(U96-GND-Pad39)") (class "Default")
      (node (ref "U96") (pin "39") (pinfunction "GND_39") (pintype "unspecified"))
    )
    (net (code "164") (name "unconnected-(U96-GPIO2-Pad3)") (class "Default")
      (node (ref "U96") (pin "3") (pinfunction "GPIO2_3") (pintype "unspecified"))
    )
    (net (code "165") (name "unconnected-(U96-GPIO3-Pad5)") (class "Default")
      (node (ref "U96") (pin "5") (pinfunction "GPIO3_5") (pintype "unspecified"))
    )
    (net (code "166") (name "unconnected-(U96-GPIO4-Pad7)") (class "Default")
      (node (ref "U96") (pin "7") (pinfunction "GPIO4_7") (pintype "unspecified"))
    )
    (net (code "167") (name "unconnected-(U96-GPIO5-Pad29)") (class "Default")
      (node (ref "U96") (pin "29") (pinfunction "GPIO5_29") (pintype "unspecified"))
    )
    (net (code "168") (name "unconnected-(U96-GPIO6-Pad31)") (class "Default")
      (node (ref "U96") (pin "31") (pinfunction "GPIO6_31") (pintype "unspecified"))
    )
    (net (code "169") (name "unconnected-(U96-GPIO7-Pad26)") (class "Default")
      (node (ref "U96") (pin "26") (pinfunction "GPIO7_26") (pintype "unspecified"))
    )
    (net (code "170") (name "unconnected-(U96-GPIO12-Pad32)") (class "Default")
      (node (ref "U96") (pin "32") (pinfunction "GPIO12_32") (pintype "unspecified"))
    )
    (net (code "171") (name "unconnected-(U96-GPIO13-Pad33)") (class "Default")
      (node (ref "U96") (pin "33") (pinfunction "GPIO13_33") (pintype "unspecified"))
    )
    (net (code "172") (name "unconnected-(U96-GPIO15-Pad10)") (class "Default")
      (node (ref "U96") (pin "10") (pinfunction "GPIO15_10") (pintype "unspecified"))
    )
    (net (code "173") (name "unconnected-(U96-GPIO18-Pad12)") (class "Default")
      (node (ref "U96") (pin "12") (pinfunction "GPIO18_12") (pintype "unspecified"))
    )
    (net (code "174") (name "unconnected-(U96-GPIO19-Pad35)") (class "Default")
      (node (ref "U96") (pin "35") (pinfunction "GPIO19_35") (pintype "unspecified"))
    )
    (net (code "175") (name "unconnected-(U96-GPIO22-Pad15)") (class "Default")
      (node (ref "U96") (pin "15") (pinfunction "GPIO22_15") (pintype "unspecified"))
    )
    (net (code "176") (name "unconnected-(U96-GPIO23-Pad16)") (class "Default")
      (node (ref "U96") (pin "16") (pinfunction "GPIO23_16") (pintype "unspecified"))
    )
    (net (code "177") (name "unconnected-(U96-GPIO24-Pad18)") (class "Default")
      (node (ref "U96") (pin "18") (pinfunction "GPIO24_18") (pintype "unspecified"))
    )
    (net (code "178") (name "unconnected-(U96-GPIO25-Pad22)") (class "Default")
      (node (ref "U96") (pin "22") (pinfunction "GPIO25_22") (pintype "unspecified"))
    )
    (net (code "179") (name "unconnected-(U96-GPIO26-Pad37)") (class "Default")
      (node (ref "U96") (pin "37") (pinfunction "GPIO26_37") (pintype "unspecified"))
    )
    (net (code "180") (name "unconnected-(U96-ID_SC-Pad28)") (class "Default")
      (node (ref "U96") (pin "28") (pinfunction "ID_SC_28") (pintype "unspecified"))
    )
    (net (code "181") (name "unconnected-(U96-ID_SD-Pad27)") (class "Default")
      (node (ref "U96") (pin "27") (pinfunction "ID_SD_27") (pintype "unspecified"))
    )
  )
)
